# Transfer_Register.net
KiCad netlist of a schematic drawn in EAGLE
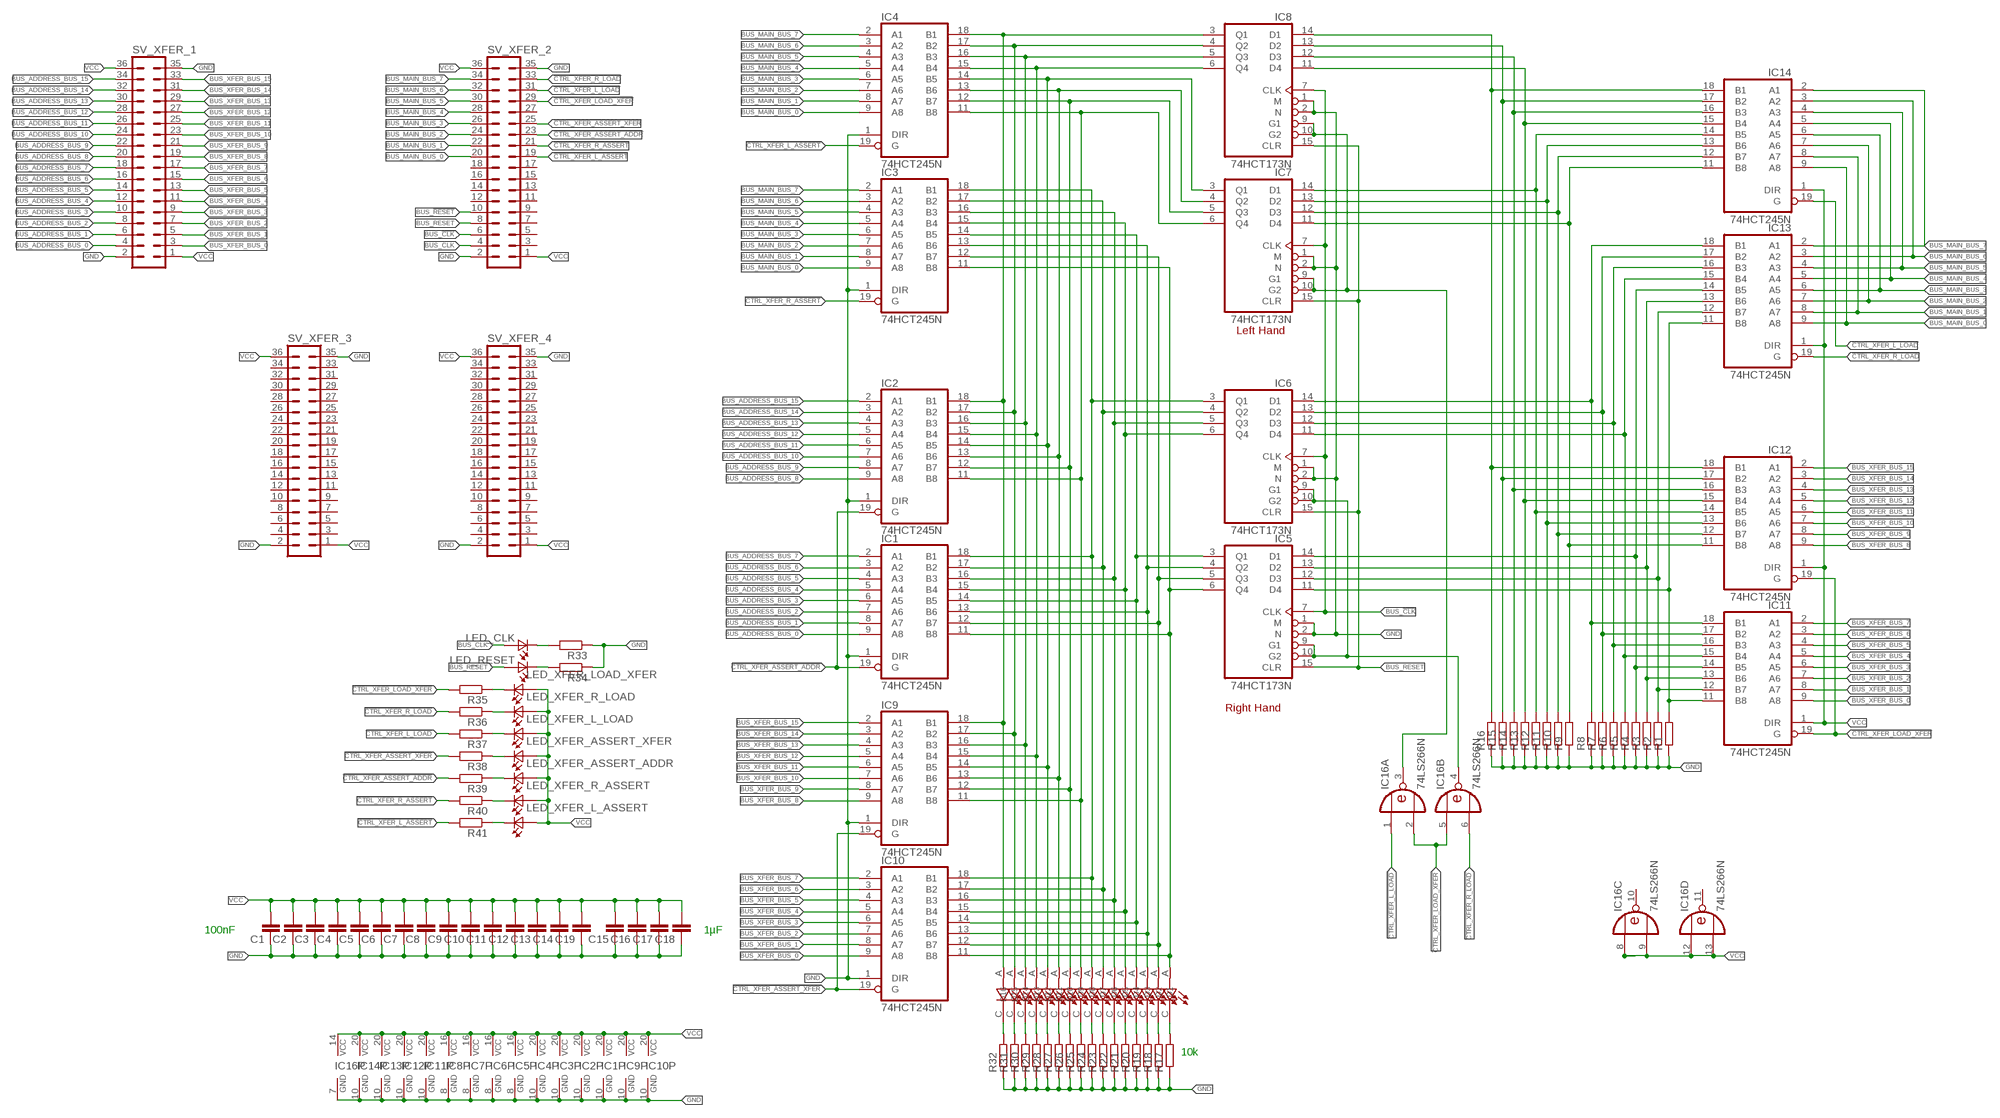
[diagram p0: schematic, sheet 1]

(export (version "E")
  (design (tool "Eeschema 10.0.6"))
  (components
    (comp (ref "C1")
      (value "C-EUC0805")
      (footprint "eagle-import:C0805")
      (libsource (lib "eagle-import") (part "C-EUC0805"))
    )
    (comp (ref "C2")
      (value "C-EUC0805")
      (footprint "eagle-import:C0805")
      (libsource (lib "eagle-import") (part "C-EUC0805"))
    )
    (comp (ref "C3")
      (value "C-EUC0805")
      (footprint "eagle-import:C0805")
      (libsource (lib "eagle-import") (part "C-EUC0805"))
    )
    (comp (ref "C4")
      (value "C-EUC0805")
      (footprint "eagle-import:C0805")
      (libsource (lib "eagle-import") (part "C-EUC0805"))
    )
    (comp (ref "C5")
      (value "C-EUC0805")
      (footprint "eagle-import:C0805")
      (libsource (lib "eagle-import") (part "C-EUC0805"))
    )
    (comp (ref "C6")
      (value "C-EUC0805")
      (footprint "eagle-import:C0805")
      (libsource (lib "eagle-import") (part "C-EUC0805"))
    )
    (comp (ref "C7")
      (value "C-EUC0805")
      (footprint "eagle-import:C0805")
      (libsource (lib "eagle-import") (part "C-EUC0805"))
    )
    (comp (ref "C8")
      (value "C-EUC0805")
      (footprint "eagle-import:C0805")
      (libsource (lib "eagle-import") (part "C-EUC0805"))
    )
    (comp (ref "C9")
      (value "C-EUC0805")
      (footprint "eagle-import:C0805")
      (libsource (lib "eagle-import") (part "C-EUC0805"))
    )
    (comp (ref "C10")
      (value "C-EUC0805")
      (footprint "eagle-import:C0805")
      (libsource (lib "eagle-import") (part "C-EUC0805"))
    )
    (comp (ref "C11")
      (value "C-EUC0805")
      (footprint "eagle-import:C0805")
      (libsource (lib "eagle-import") (part "C-EUC0805"))
    )
    (comp (ref "C12")
      (value "C-EUC0805")
      (footprint "eagle-import:C0805")
      (libsource (lib "eagle-import") (part "C-EUC0805"))
    )
    (comp (ref "C13")
      (value "C-EUC0805")
      (footprint "eagle-import:C0805")
      (libsource (lib "eagle-import") (part "C-EUC0805"))
    )
    (comp (ref "C14")
      (value "C-EUC0805")
      (footprint "eagle-import:C0805")
      (libsource (lib "eagle-import") (part "C-EUC0805"))
    )
    (comp (ref "C15")
      (value "C-EUC0805")
      (footprint "eagle-import:C0805")
      (libsource (lib "eagle-import") (part "C-EUC0805"))
    )
    (comp (ref "C16")
      (value "C-EUC0805")
      (footprint "eagle-import:C0805")
      (libsource (lib "eagle-import") (part "C-EUC0805"))
    )
    (comp (ref "C17")
      (value "C-EUC0805")
      (footprint "eagle-import:C0805")
      (libsource (lib "eagle-import") (part "C-EUC0805"))
    )
    (comp (ref "C18")
      (value "C-EUC0805")
      (footprint "eagle-import:C0805")
      (libsource (lib "eagle-import") (part "C-EUC0805"))
    )
    (comp (ref "C19")
      (value "C-EUC0805")
      (footprint "eagle-import:C0805")
      (libsource (lib "eagle-import") (part "C-EUC0805"))
    )
    (comp (ref "D1")
      (value "LTST-C193KRKT-5A")
      (footprint "eagle-import:LEDC1608X45N")
      (fields (field (name "MANUFACTURER") "Lite-On"))
      (libsource (lib "eagle-import") (part "LTST-C193KRKT-5A"))
    )
    (comp (ref "D2")
      (value "LTST-C193KRKT-5A")
      (footprint "eagle-import:LEDC1608X45N")
      (fields (field (name "MANUFACTURER") "Lite-On"))
      (libsource (lib "eagle-import") (part "LTST-C193KRKT-5A"))
    )
    (comp (ref "D3")
      (value "LTST-C193KRKT-5A")
      (footprint "eagle-import:LEDC1608X45N")
      (fields (field (name "MANUFACTURER") "Lite-On"))
      (libsource (lib "eagle-import") (part "LTST-C193KRKT-5A"))
    )
    (comp (ref "D4")
      (value "LTST-C193KRKT-5A")
      (footprint "eagle-import:LEDC1608X45N")
      (fields (field (name "MANUFACTURER") "Lite-On"))
      (libsource (lib "eagle-import") (part "LTST-C193KRKT-5A"))
    )
    (comp (ref "D5")
      (value "LTST-C193KRKT-5A")
      (footprint "eagle-import:LEDC1608X45N")
      (fields (field (name "MANUFACTURER") "Lite-On"))
      (libsource (lib "eagle-import") (part "LTST-C193KRKT-5A"))
    )
    (comp (ref "D6")
      (value "LTST-C193KRKT-5A")
      (footprint "eagle-import:LEDC1608X45N")
      (fields (field (name "MANUFACTURER") "Lite-On"))
      (libsource (lib "eagle-import") (part "LTST-C193KRKT-5A"))
    )
    (comp (ref "D7")
      (value "LTST-C193KRKT-5A")
      (footprint "eagle-import:LEDC1608X45N")
      (fields (field (name "MANUFACTURER") "Lite-On"))
      (libsource (lib "eagle-import") (part "LTST-C193KRKT-5A"))
    )
    (comp (ref "D8")
      (value "LTST-C193KRKT-5A")
      (footprint "eagle-import:LEDC1608X45N")
      (fields (field (name "MANUFACTURER") "Lite-On"))
      (libsource (lib "eagle-import") (part "LTST-C193KRKT-5A"))
    )
    (comp (ref "D9")
      (value "LTST-C193KRKT-5A")
      (footprint "eagle-import:LEDC1608X45N")
      (fields (field (name "MANUFACTURER") "Lite-On"))
      (libsource (lib "eagle-import") (part "LTST-C193KRKT-5A"))
    )
    (comp (ref "D10")
      (value "LTST-C193KRKT-5A")
      (footprint "eagle-import:LEDC1608X45N")
      (fields (field (name "MANUFACTURER") "Lite-On"))
      (libsource (lib "eagle-import") (part "LTST-C193KRKT-5A"))
    )
    (comp (ref "D11")
      (value "LTST-C193KRKT-5A")
      (footprint "eagle-import:LEDC1608X45N")
      (fields (field (name "MANUFACTURER") "Lite-On"))
      (libsource (lib "eagle-import") (part "LTST-C193KRKT-5A"))
    )
    (comp (ref "D12")
      (value "LTST-C193KRKT-5A")
      (footprint "eagle-import:LEDC1608X45N")
      (fields (field (name "MANUFACTURER") "Lite-On"))
      (libsource (lib "eagle-import") (part "LTST-C193KRKT-5A"))
    )
    (comp (ref "D13")
      (value "LTST-C193KRKT-5A")
      (footprint "eagle-import:LEDC1608X45N")
      (fields (field (name "MANUFACTURER") "Lite-On"))
      (libsource (lib "eagle-import") (part "LTST-C193KRKT-5A"))
    )
    (comp (ref "D14")
      (value "LTST-C193KRKT-5A")
      (footprint "eagle-import:LEDC1608X45N")
      (fields (field (name "MANUFACTURER") "Lite-On"))
      (libsource (lib "eagle-import") (part "LTST-C193KRKT-5A"))
    )
    (comp (ref "D15")
      (value "LTST-C193KRKT-5A")
      (footprint "eagle-import:LEDC1608X45N")
      (fields (field (name "MANUFACTURER") "Lite-On"))
      (libsource (lib "eagle-import") (part "LTST-C193KRKT-5A"))
    )
    (comp (ref "D16")
      (value "LTST-C193KRKT-5A")
      (footprint "eagle-import:LEDC1608X45N")
      (fields (field (name "MANUFACTURER") "Lite-On"))
      (libsource (lib "eagle-import") (part "LTST-C193KRKT-5A"))
    )
    (comp (ref "IC1")
      (value "74HCT245N")
      (footprint "eagle-import:DIL20")
      (libsource (lib "eagle-import") (part "74245NHCT"))
    )
    (comp (ref "IC2")
      (value "74HCT245N")
      (footprint "eagle-import:DIL20")
      (libsource (lib "eagle-import") (part "74245NHCT"))
    )
    (comp (ref "IC3")
      (value "74HCT245N")
      (footprint "eagle-import:DIL20")
      (libsource (lib "eagle-import") (part "74245NHCT"))
    )
    (comp (ref "IC4")
      (value "74HCT245N")
      (footprint "eagle-import:DIL20")
      (libsource (lib "eagle-import") (part "74245NHCT"))
    )
    (comp (ref "IC5")
      (value "74HCT173N")
      (footprint "eagle-import:DIL16")
      (libsource (lib "eagle-import") (part "74173NHCT"))
    )
    (comp (ref "IC6")
      (value "74HCT173N")
      (footprint "eagle-import:DIL16")
      (libsource (lib "eagle-import") (part "74173NHCT"))
    )
    (comp (ref "IC7")
      (value "74HCT173N")
      (footprint "eagle-import:DIL16")
      (libsource (lib "eagle-import") (part "74173NHCT"))
    )
    (comp (ref "IC8")
      (value "74HCT173N")
      (footprint "eagle-import:DIL16")
      (libsource (lib "eagle-import") (part "74173NHCT"))
    )
    (comp (ref "IC9")
      (value "74HCT245N")
      (footprint "eagle-import:DIL20")
      (libsource (lib "eagle-import") (part "74245NHCT"))
    )
    (comp (ref "IC10")
      (value "74HCT245N")
      (footprint "eagle-import:DIL20")
      (libsource (lib "eagle-import") (part "74245NHCT"))
    )
    (comp (ref "IC11")
      (value "74HCT245N")
      (footprint "eagle-import:DIL20")
      (libsource (lib "eagle-import") (part "74245NHCT"))
    )
    (comp (ref "IC12")
      (value "74HCT245N")
      (footprint "eagle-import:DIL20")
      (libsource (lib "eagle-import") (part "74245NHCT"))
    )
    (comp (ref "IC13")
      (value "74HCT245N")
      (footprint "eagle-import:DIL20")
      (libsource (lib "eagle-import") (part "74245NHCT"))
    )
    (comp (ref "IC14")
      (value "74HCT245N")
      (footprint "eagle-import:DIL20")
      (libsource (lib "eagle-import") (part "74245NHCT"))
    )
    (comp (ref "IC16")
      (value "74LS266N")
      (footprint "eagle-import:DIL14")
      (libsource (lib "eagle-import") (part "74266NLS"))
    )
    (comp (ref "LED_CLK")
      (value "LTST-C193TBKT-5A")
      (footprint "eagle-import:0603")
      (libsource (lib "eagle-import") (part "LTST-C193TBKT-5A"))
    )
    (comp (ref "LED_RESET")
      (value "LTST-C193TBKT-5A")
      (footprint "eagle-import:0603")
      (libsource (lib "eagle-import") (part "LTST-C193TBKT-5A"))
    )
    (comp (ref "LED_XFER_ASSERT_ADDR")
      (value "LTST-C193TBKT-5A")
      (footprint "eagle-import:0603")
      (libsource (lib "eagle-import") (part "LTST-C193TBKT-5A"))
    )
    (comp (ref "LED_XFER_ASSERT_XFER")
      (value "LTST-C193TBKT-5A")
      (footprint "eagle-import:0603")
      (libsource (lib "eagle-import") (part "LTST-C193TBKT-5A"))
    )
    (comp (ref "LED_XFER_LOAD_XFER")
      (value "LTST-C193TBKT-5A")
      (footprint "eagle-import:0603")
      (libsource (lib "eagle-import") (part "LTST-C193TBKT-5A"))
    )
    (comp (ref "LED_XFER_L_ASSERT")
      (value "LTST-C193TBKT-5A")
      (footprint "eagle-import:0603")
      (libsource (lib "eagle-import") (part "LTST-C193TBKT-5A"))
    )
    (comp (ref "LED_XFER_L_LOAD")
      (value "LTST-C193TBKT-5A")
      (footprint "eagle-import:0603")
      (libsource (lib "eagle-import") (part "LTST-C193TBKT-5A"))
    )
    (comp (ref "LED_XFER_R_ASSERT")
      (value "LTST-C193TBKT-5A")
      (footprint "eagle-import:0603")
      (libsource (lib "eagle-import") (part "LTST-C193TBKT-5A"))
    )
    (comp (ref "LED_XFER_R_LOAD")
      (value "LTST-C193TBKT-5A")
      (footprint "eagle-import:0603")
      (libsource (lib "eagle-import") (part "LTST-C193TBKT-5A"))
    )
    (comp (ref "R1")
      (value "R-EU_R0805")
      (footprint "eagle-import:R0805")
      (libsource (lib "eagle-import") (part "R-EU_R0805"))
    )
    (comp (ref "R2")
      (value "R-EU_R0805")
      (footprint "eagle-import:R0805")
      (libsource (lib "eagle-import") (part "R-EU_R0805"))
    )
    (comp (ref "R3")
      (value "R-EU_R0805")
      (footprint "eagle-import:R0805")
      (libsource (lib "eagle-import") (part "R-EU_R0805"))
    )
    (comp (ref "R4")
      (value "R-EU_R0805")
      (footprint "eagle-import:R0805")
      (libsource (lib "eagle-import") (part "R-EU_R0805"))
    )
    (comp (ref "R5")
      (value "R-EU_R0805")
      (footprint "eagle-import:R0805")
      (libsource (lib "eagle-import") (part "R-EU_R0805"))
    )
    (comp (ref "R6")
      (value "R-EU_R0805")
      (footprint "eagle-import:R0805")
      (libsource (lib "eagle-import") (part "R-EU_R0805"))
    )
    (comp (ref "R7")
      (value "R-EU_R0805")
      (footprint "eagle-import:R0805")
      (libsource (lib "eagle-import") (part "R-EU_R0805"))
    )
    (comp (ref "R8")
      (value "R-EU_R0805")
      (footprint "eagle-import:R0805")
      (libsource (lib "eagle-import") (part "R-EU_R0805"))
    )
    (comp (ref "R9")
      (value "R-EU_R0805")
      (footprint "eagle-import:R0805")
      (libsource (lib "eagle-import") (part "R-EU_R0805"))
    )
    (comp (ref "R10")
      (value "R-EU_R0805")
      (footprint "eagle-import:R0805")
      (libsource (lib "eagle-import") (part "R-EU_R0805"))
    )
    (comp (ref "R11")
      (value "R-EU_R0805")
      (footprint "eagle-import:R0805")
      (libsource (lib "eagle-import") (part "R-EU_R0805"))
    )
    (comp (ref "R12")
      (value "R-EU_R0805")
      (footprint "eagle-import:R0805")
      (libsource (lib "eagle-import") (part "R-EU_R0805"))
    )
    (comp (ref "R13")
      (value "R-EU_R0805")
      (footprint "eagle-import:R0805")
      (libsource (lib "eagle-import") (part "R-EU_R0805"))
    )
    (comp (ref "R14")
      (value "R-EU_R0805")
      (footprint "eagle-import:R0805")
      (libsource (lib "eagle-import") (part "R-EU_R0805"))
    )
    (comp (ref "R15")
      (value "R-EU_R0805")
      (footprint "eagle-import:R0805")
      (libsource (lib "eagle-import") (part "R-EU_R0805"))
    )
    (comp (ref "R16")
      (value "R-EU_R0805")
      (footprint "eagle-import:R0805")
      (libsource (lib "eagle-import") (part "R-EU_R0805"))
    )
    (comp (ref "R17")
      (value "R-EU_R0805")
      (footprint "eagle-import:R0805")
      (libsource (lib "eagle-import") (part "R-EU_R0805"))
    )
    (comp (ref "R18")
      (value "R-EU_R0805")
      (footprint "eagle-import:R0805")
      (libsource (lib "eagle-import") (part "R-EU_R0805"))
    )
    (comp (ref "R19")
      (value "R-EU_R0805")
      (footprint "eagle-import:R0805")
      (libsource (lib "eagle-import") (part "R-EU_R0805"))
    )
    (comp (ref "R20")
      (value "R-EU_R0805")
      (footprint "eagle-import:R0805")
      (libsource (lib "eagle-import") (part "R-EU_R0805"))
    )
    (comp (ref "R21")
      (value "R-EU_R0805")
      (footprint "eagle-import:R0805")
      (libsource (lib "eagle-import") (part "R-EU_R0805"))
    )
    (comp (ref "R22")
      (value "R-EU_R0805")
      (footprint "eagle-import:R0805")
      (libsource (lib "eagle-import") (part "R-EU_R0805"))
    )
    (comp (ref "R23")
      (value "R-EU_R0805")
      (footprint "eagle-import:R0805")
      (libsource (lib "eagle-import") (part "R-EU_R0805"))
    )
    (comp (ref "R24")
      (value "R-EU_R0805")
      (footprint "eagle-import:R0805")
      (libsource (lib "eagle-import") (part "R-EU_R0805"))
    )
    (comp (ref "R25")
      (value "R-EU_R0805")
      (footprint "eagle-import:R0805")
      (libsource (lib "eagle-import") (part "R-EU_R0805"))
    )
    (comp (ref "R26")
      (value "R-EU_R0805")
      (footprint "eagle-import:R0805")
      (libsource (lib "eagle-import") (part "R-EU_R0805"))
    )
    (comp (ref "R27")
      (value "R-EU_R0805")
      (footprint "eagle-import:R0805")
      (libsource (lib "eagle-import") (part "R-EU_R0805"))
    )
    (comp (ref "R28")
      (value "R-EU_R0805")
      (footprint "eagle-import:R0805")
      (libsource (lib "eagle-import") (part "R-EU_R0805"))
    )
    (comp (ref "R29")
      (value "R-EU_R0805")
      (footprint "eagle-import:R0805")
      (libsource (lib "eagle-import") (part "R-EU_R0805"))
    )
    (comp (ref "R30")
      (value "R-EU_R0805")
      (footprint "eagle-import:R0805")
      (libsource (lib "eagle-import") (part "R-EU_R0805"))
    )
    (comp (ref "R31")
      (value "R-EU_R0805")
      (footprint "eagle-import:R0805")
      (libsource (lib "eagle-import") (part "R-EU_R0805"))
    )
    (comp (ref "R32")
      (value "R-EU_R0805")
      (footprint "eagle-import:R0805")
      (libsource (lib "eagle-import") (part "R-EU_R0805"))
    )
    (comp (ref "R33")
      (value "R-EU_R0805")
      (footprint "eagle-import:R0805")
      (libsource (lib "eagle-import") (part "R-EU_R0805"))
    )
    (comp (ref "R34")
      (value "R-EU_R0805")
      (footprint "eagle-import:R0805")
      (libsource (lib "eagle-import") (part "R-EU_R0805"))
    )
    (comp (ref "R35")
      (value "R-EU_R0805")
      (footprint "eagle-import:R0805")
      (libsource (lib "eagle-import") (part "R-EU_R0805"))
    )
    (comp (ref "R36")
      (value "R-EU_R0805")
      (footprint "eagle-import:R0805")
      (libsource (lib "eagle-import") (part "R-EU_R0805"))
    )
    (comp (ref "R37")
      (value "R-EU_R0805")
      (footprint "eagle-import:R0805")
      (libsource (lib "eagle-import") (part "R-EU_R0805"))
    )
    (comp (ref "R38")
      (value "R-EU_R0805")
      (footprint "eagle-import:R0805")
      (libsource (lib "eagle-import") (part "R-EU_R0805"))
    )
    (comp (ref "R39")
      (value "R-EU_R0805")
      (footprint "eagle-import:R0805")
      (libsource (lib "eagle-import") (part "R-EU_R0805"))
    )
    (comp (ref "R40")
      (value "R-EU_R0805")
      (footprint "eagle-import:R0805")
      (libsource (lib "eagle-import") (part "R-EU_R0805"))
    )
    (comp (ref "R41")
      (value "R-EU_R0805")
      (footprint "eagle-import:R0805")
      (libsource (lib "eagle-import") (part "R-EU_R0805"))
    )
    (comp (ref "SV_XFER_1")
      (value "MA18-2")
      (footprint "eagle-import:MA18-2")
      (libsource (lib "eagle-import") (part "MA18-2"))
    )
    (comp (ref "SV_XFER_2")
      (value "MA18-2")
      (footprint "eagle-import:MA18-2")
      (libsource (lib "eagle-import") (part "MA18-2"))
    )
    (comp (ref "SV_XFER_3")
      (value "MA18-2")
      (footprint "eagle-import:MA18-2")
      (libsource (lib "eagle-import") (part "MA18-2"))
    )
    (comp (ref "SV_XFER_4")
      (value "MA18-2")
      (footprint "eagle-import:MA18-2")
      (libsource (lib "eagle-import") (part "MA18-2"))
    )
  )
  (nets
    (net (code "1") (name "/BUS_~{CLK}") (class "Default")
      (node (ref "IC5") (pin "7") (pinfunction "CLK_7") (pintype "input"))
      (node (ref "IC6") (pin "7") (pinfunction "CLK_7") (pintype "input"))
      (node (ref "IC7") (pin "7") (pinfunction "CLK_7") (pintype "input"))
      (node (ref "IC8") (pin "7") (pinfunction "CLK_7") (pintype "input"))
      (node (ref "SV_XFER_2") (pin "6") (pinfunction "6_6") (pintype "passive"))
    )
    (net (code "2") (name "/BUS_~{RESET}") (class "Default")
      (node (ref "SV_XFER_2") (pin "10") (pinfunction "10_10") (pintype "passive"))
    )
    (net (code "3") (name "/~{CTRL_XFER_ASSERT_ADDR}") (class "Default")
      (node (ref "IC1") (pin "19") (pinfunction "G_19") (pintype "input"))
      (node (ref "IC2") (pin "19") (pinfunction "G_19") (pintype "input"))
      (node (ref "R39") (pin "2") (pinfunction "2_2") (pintype "passive"))
      (node (ref "SV_XFER_2") (pin "23") (pinfunction "23_23") (pintype "passive"))
    )
    (net (code "4") (name "/~{CTRL_XFER_ASSERT_XFER}") (class "Default")
      (node (ref "IC10") (pin "19") (pinfunction "G_19") (pintype "input"))
      (node (ref "IC9") (pin "19") (pinfunction "G_19") (pintype "input"))
      (node (ref "R38") (pin "2") (pinfunction "2_2") (pintype "passive"))
      (node (ref "SV_XFER_2") (pin "25") (pinfunction "25_25") (pintype "passive"))
    )
    (net (code "5") (name "/~{CTRL_XFER_LOAD_XFER}") (class "Default")
      (node (ref "IC11") (pin "19") (pinfunction "G_19") (pintype "input"))
      (node (ref "IC12") (pin "19") (pinfunction "G_19") (pintype "input"))
      (node (ref "IC16") (pin "2") (pinfunction "I1_2") (pintype "input"))
      (node (ref "IC16") (pin "5") (pinfunction "I0_5") (pintype "input"))
      (node (ref "R35") (pin "2") (pinfunction "2_2") (pintype "passive"))
      (node (ref "SV_XFER_2") (pin "29") (pinfunction "29_29") (pintype "passive"))
    )
    (net (code "6") (name "/~{CTRL_XFER_L_ASSERT}") (class "Default")
      (node (ref "IC4") (pin "19") (pinfunction "G_19") (pintype "input"))
      (node (ref "R41") (pin "2") (pinfunction "2_2") (pintype "passive"))
      (node (ref "SV_XFER_2") (pin "19") (pinfunction "19_19") (pintype "passive"))
    )
    (net (code "7") (name "/~{CTRL_XFER_L_LOAD}") (class "Default")
      (node (ref "IC14") (pin "19") (pinfunction "G_19") (pintype "input"))
      (node (ref "IC16") (pin "1") (pinfunction "I0_1") (pintype "input"))
      (node (ref "R37") (pin "2") (pinfunction "2_2") (pintype "passive"))
      (node (ref "SV_XFER_2") (pin "31") (pinfunction "31_31") (pintype "passive"))
    )
    (net (code "8") (name "/~{CTRL_XFER_R_ASSERT}") (class "Default")
      (node (ref "IC3") (pin "19") (pinfunction "G_19") (pintype "input"))
      (node (ref "R40") (pin "2") (pinfunction "2_2") (pintype "passive"))
      (node (ref "SV_XFER_2") (pin "21") (pinfunction "21_21") (pintype "passive"))
    )
    (net (code "9") (name "/~{CTRL_XFER_R_LOAD}") (class "Default")
      (node (ref "IC13") (pin "19") (pinfunction "G_19") (pintype "input"))
      (node (ref "IC16") (pin "6") (pinfunction "I1_6") (pintype "input"))
      (node (ref "R36") (pin "2") (pinfunction "2_2") (pintype "passive"))
      (node (ref "SV_XFER_2") (pin "33") (pinfunction "33_33") (pintype "passive"))
    )
    (net (code "10") (name "BUS_ADDRESS_BUS_0") (class "Default")
      (node (ref "IC1") (pin "9") (pinfunction "A8_9") (pintype "bidirectional"))
      (node (ref "SV_XFER_1") (pin "4") (pinfunction "4_4") (pintype "passive"))
    )
    (net (code "11") (name "BUS_ADDRESS_BUS_1") (class "Default")
      (node (ref "IC1") (pin "8") (pinfunction "A7_8") (pintype "bidirectional"))
      (node (ref "SV_XFER_1") (pin "6") (pinfunction "6_6") (pintype "passive"))
    )
    (net (code "12") (name "BUS_ADDRESS_BUS_2") (class "Default")
      (node (ref "IC1") (pin "7") (pinfunction "A6_7") (pintype "bidirectional"))
      (node (ref "SV_XFER_1") (pin "8") (pinfunction "8_8") (pintype "passive"))
    )
    (net (code "13") (name "BUS_ADDRESS_BUS_3") (class "Default")
      (node (ref "IC1") (pin "6") (pinfunction "A5_6") (pintype "bidirectional"))
      (node (ref "SV_XFER_1") (pin "10") (pinfunction "10_10") (pintype "passive"))
    )
    (net (code "14") (name "BUS_ADDRESS_BUS_4") (class "Default")
      (node (ref "IC1") (pin "5") (pinfunction "A4_5") (pintype "bidirectional"))
      (node (ref "SV_XFER_1") (pin "12") (pinfunction "12_12") (pintype "passive"))
    )
    (net (code "15") (name "BUS_ADDRESS_BUS_5") (class "Default")
      (node (ref "IC1") (pin "4") (pinfunction "A3_4") (pintype "bidirectional"))
      (node (ref "SV_XFER_1") (pin "14") (pinfunction "14_14") (pintype "passive"))
    )
    (net (code "16") (name "BUS_ADDRESS_BUS_6") (class "Default")
      (node (ref "IC1") (pin "3") (pinfunction "A2_3") (pintype "bidirectional"))
      (node (ref "SV_XFER_1") (pin "16") (pinfunction "16_16") (pintype "passive"))
    )
    (net (code "17") (name "BUS_ADDRESS_BUS_7") (class "Default")
      (node (ref "IC1") (pin "2") (pinfunction "A1_2") (pintype "bidirectional"))
      (node (ref "SV_XFER_1") (pin "18") (pinfunction "18_18") (pintype "passive"))
    )
    (net (code "18") (name "BUS_ADDRESS_BUS_8") (class "Default")
      (node (ref "IC2") (pin "9") (pinfunction "A8_9") (pintype "bidirectional"))
      (node (ref "SV_XFER_1") (pin "20") (pinfunction "20_20") (pintype "passive"))
    )
    (net (code "19") (name "BUS_ADDRESS_BUS_9") (class "Default")
      (node (ref "IC2") (pin "8") (pinfunction "A7_8") (pintype "bidirectional"))
      (node (ref "SV_XFER_1") (pin "22") (pinfunction "22_22") (pintype "passive"))
    )
    (net (code "20") (name "BUS_ADDRESS_BUS_10") (class "Default")
      (node (ref "IC2") (pin "7") (pinfunction "A6_7") (pintype "bidirectional"))
      (node (ref "SV_XFER_1") (pin "24") (pinfunction "24_24") (pintype "passive"))
    )
    (net (code "21") (name "BUS_ADDRESS_BUS_11") (class "Default")
      (node (ref "IC2") (pin "6") (pinfunction "A5_6") (pintype "bidirectional"))
      (node (ref "SV_XFER_1") (pin "26") (pinfunction "26_26") (pintype "passive"))
    )
    (net (code "22") (name "BUS_ADDRESS_BUS_12") (class "Default")
      (node (ref "IC2") (pin "5") (pinfunction "A4_5") (pintype "bidirectional"))
      (node (ref "SV_XFER_1") (pin "28") (pinfunction "28_28") (pintype "passive"))
    )
    (net (code "23") (name "BUS_ADDRESS_BUS_13") (class "Default")
      (node (ref "IC2") (pin "4") (pinfunction "A3_4") (pintype "bidirectional"))
      (node (ref "SV_XFER_1") (pin "30") (pinfunction "30_30") (pintype "passive"))
    )
    (net (code "24") (name "BUS_ADDRESS_BUS_14") (class "Default")
      (node (ref "IC2") (pin "3") (pinfunction "A2_3") (pintype "bidirectional"))
      (node (ref "SV_XFER_1") (pin "32") (pinfunction "32_32") (pintype "passive"))
    )
    (net (code "25") (name "BUS_ADDRESS_BUS_15") (class "Default")
      (node (ref "IC2") (pin "2") (pinfunction "A1_2") (pintype "bidirectional"))
      (node (ref "SV_XFER_1") (pin "34") (pinfunction "34_34") (pintype "passive"))
    )
    (net (code "26") (name "BUS_CLK") (class "Default")
      (node (ref "LED_CLK") (pin "2") (pinfunction "A2_2") (pintype "passive"))
      (node (ref "SV_XFER_2") (pin "4") (pinfunction "4_4") (pintype "passive"))
    )
    (net (code "27") (name "BUS_MAIN_BUS_0") (class "Default")
      (node (ref "IC13") (pin "9") (pinfunction "A8_9") (pintype "bidirectional"))
      (node (ref "IC14") (pin "9") (pinfunction "A8_9") (pintype "bidirectional"))
      (node (ref "IC3") (pin "9") (pinfunction "A8_9") (pintype "bidirectional"))
      (node (ref "IC4") (pin "9") (pinfunction "A8_9") (pintype "bidirectional"))
      (node (ref "SV_XFER_2") (pin "20") (pinfunction "20_20") (pintype "passive"))
    )
    (net (code "28") (name "BUS_MAIN_BUS_1") (class "Default")
      (node (ref "IC13") (pin "8") (pinfunction "A7_8") (pintype "bidirectional"))
      (node (ref "IC14") (pin "8") (pinfunction "A7_8") (pintype "bidirectional"))
      (node (ref "IC3") (pin "8") (pinfunction "A7_8") (pintype "bidirectional"))
      (node (ref "IC4") (pin "8") (pinfunction "A7_8") (pintype "bidirectional"))
      (node (ref "SV_XFER_2") (pin "22") (pinfunction "22_22") (pintype "passive"))
    )
    (net (code "29") (name "BUS_MAIN_BUS_2") (class "Default")
      (node (ref "IC13") (pin "7") (pinfunction "A6_7") (pintype "bidirectional"))
      (node (ref "IC14") (pin "7") (pinfunction "A6_7") (pintype "bidirectional"))
      (node (ref "IC3") (pin "7") (pinfunction "A6_7") (pintype "bidirectional"))
      (node (ref "IC4") (pin "7") (pinfunction "A6_7") (pintype "bidirectional"))
      (node (ref "SV_XFER_2") (pin "24") (pinfunction "24_24") (pintype "passive"))
    )
    (net (code "30") (name "BUS_MAIN_BUS_3") (class "Default")
      (node (ref "IC13") (pin "6") (pinfunction "A5_6") (pintype "bidirectional"))
      (node (ref "IC14") (pin "6") (pinfunction "A5_6") (pintype "bidirectional"))
      (node (ref "IC3") (pin "6") (pinfunction "A5_6") (pintype "bidirectional"))
      (node (ref "IC4") (pin "6") (pinfunction "A5_6") (pintype "bidirectional"))
      (node (ref "SV_XFER_2") (pin "26") (pinfunction "26_26") (pintype "passive"))
    )
    (net (code "31") (name "BUS_MAIN_BUS_4") (class "Default")
      (node (ref "IC13") (pin "5") (pinfunction "A4_5") (pintype "bidirectional"))
      (node (ref "IC14") (pin "5") (pinfunction "A4_5") (pintype "bidirectional"))
      (node (ref "IC3") (pin "5") (pinfunction "A4_5") (pintype "bidirectional"))
      (node (ref "IC4") (pin "5") (pinfunction "A4_5") (pintype "bidirectional"))
      (node (ref "SV_XFER_2") (pin "28") (pinfunction "28_28") (pintype "passive"))
    )
    (net (code "32") (name "BUS_MAIN_BUS_5") (class "Default")
      (node (ref "IC13") (pin "4") (pinfunction "A3_4") (pintype "bidirectional"))
      (node (ref "IC14") (pin "4") (pinfunction "A3_4") (pintype "bidirectional"))
      (node (ref "IC3") (pin "4") (pinfunction "A3_4") (pintype "bidirectional"))
      (node (ref "IC4") (pin "4") (pinfunction "A3_4") (pintype "bidirectional"))
      (node (ref "SV_XFER_2") (pin "30") (pinfunction "30_30") (pintype "passive"))
    )
    (net (code "33") (name "BUS_MAIN_BUS_6") (class "Default")
      (node (ref "IC13") (pin "3") (pinfunction "A2_3") (pintype "bidirectional"))
      (node (ref "IC14") (pin "3") (pinfunction "A2_3") (pintype "bidirectional"))
      (node (ref "IC3") (pin "3") (pinfunction "A2_3") (pintype "bidirectional"))
      (node (ref "IC4") (pin "3") (pinfunction "A2_3") (pintype "bidirectional"))
      (node (ref "SV_XFER_2") (pin "32") (pinfunction "32_32") (pintype "passive"))
    )
    (net (code "34") (name "BUS_MAIN_BUS_7") (class "Default")
      (node (ref "IC13") (pin "2") (pinfunction "A1_2") (pintype "bidirectional"))
      (node (ref "IC14") (pin "2") (pinfunction "A1_2") (pintype "bidirectional"))
      (node (ref "IC3") (pin "2") (pinfunction "A1_2") (pintype "bidirectional"))
      (node (ref "IC4") (pin "2") (pinfunction "A1_2") (pintype "bidirectional"))
      (node (ref "SV_XFER_2") (pin "34") (pinfunction "34_34") (pintype "passive"))
    )
    (net (code "35") (name "BUS_RESET") (class "Default")
      (node (ref "IC5") (pin "15") (pinfunction "CLR_15") (pintype "input"))
      (node (ref "IC6") (pin "15") (pinfunction "CLR_15") (pintype "input"))
      (node (ref "IC7") (pin "15") (pinfunction "CLR_15") (pintype "input"))
      (node (ref "IC8") (pin "15") (pinfunction "CLR_15") (pintype "input"))
      (node (ref "LED_RESET") (pin "2") (pinfunction "A2_2") (pintype "passive"))
      (node (ref "SV_XFER_2") (pin "8") (pinfunction "8_8") (pintype "passive"))
    )
    (net (code "36") (name "BUS_XFER_BUS_0") (class "Default")
      (node (ref "IC10") (pin "9") (pinfunction "A8_9") (pintype "bidirectional"))
      (node (ref "IC11") (pin "9") (pinfunction "A8_9") (pintype "bidirectional"))
      (node (ref "SV_XFER_1") (pin "3") (pinfunction "3_3") (pintype "passive"))
    )
    (net (code "37") (name "BUS_XFER_BUS_1") (class "Default")
      (node (ref "IC10") (pin "8") (pinfunction "A7_8") (pintype "bidirectional"))
      (node (ref "IC11") (pin "8") (pinfunction "A7_8") (pintype "bidirectional"))
      (node (ref "SV_XFER_1") (pin "5") (pinfunction "5_5") (pintype "passive"))
    )
    (net (code "38") (name "BUS_XFER_BUS_2") (class "Default")
      (node (ref "IC10") (pin "7") (pinfunction "A6_7") (pintype "bidirectional"))
      (node (ref "IC11") (pin "7") (pinfunction "A6_7") (pintype "bidirectional"))
      (node (ref "SV_XFER_1") (pin "7") (pinfunction "7_7") (pintype "passive"))
    )
    (net (code "39") (name "BUS_XFER_BUS_3") (class "Default")
      (node (ref "IC10") (pin "6") (pinfunction "A5_6") (pintype "bidirectional"))
      (node (ref "IC11") (pin "6") (pinfunction "A5_6") (pintype "bidirectional"))
      (node (ref "SV_XFER_1") (pin "9") (pinfunction "9_9") (pintype "passive"))
    )
    (net (code "40") (name "BUS_XFER_BUS_4") (class "Default")
      (node (ref "IC10") (pin "5") (pinfunction "A4_5") (pintype "bidirectional"))
      (node (ref "IC11") (pin "5") (pinfunction "A4_5") (pintype "bidirectional"))
      (node (ref "SV_XFER_1") (pin "11") (pinfunction "11_11") (pintype "passive"))
    )
    (net (code "41") (name "BUS_XFER_BUS_5") (class "Default")
      (node (ref "IC10") (pin "4") (pinfunction "A3_4") (pintype "bidirectional"))
      (node (ref "IC11") (pin "4") (pinfunction "A3_4") (pintype "bidirectional"))
      (node (ref "SV_XFER_1") (pin "13") (pinfunction "13_13") (pintype "passive"))
    )
    (net (code "42") (name "BUS_XFER_BUS_6") (class "Default")
      (node (ref "IC10") (pin "3") (pinfunction "A2_3") (pintype "bidirectional"))
      (node (ref "IC11") (pin "3") (pinfunction "A2_3") (pintype "bidirectional"))
      (node (ref "SV_XFER_1") (pin "15") (pinfunction "15_15") (pintype "passive"))
    )
    (net (code "43") (name "BUS_XFER_BUS_7") (class "Default")
      (node (ref "IC10") (pin "2") (pinfunction "A1_2") (pintype "bidirectional"))
      (node (ref "IC11") (pin "2") (pinfunction "A1_2") (pintype "bidirectional"))
      (node (ref "SV_XFER_1") (pin "17") (pinfunction "17_17") (pintype "passive"))
    )
    (net (code "44") (name "BUS_XFER_BUS_8") (class "Default")
      (node (ref "IC12") (pin "9") (pinfunction "A8_9") (pintype "bidirectional"))
      (node (ref "IC9") (pin "9") (pinfunction "A8_9") (pintype "bidirectional"))
      (node (ref "SV_XFER_1") (pin "19") (pinfunction "19_19") (pintype "passive"))
    )
    (net (code "45") (name "BUS_XFER_BUS_9") (class "Default")
      (node (ref "IC12") (pin "8") (pinfunction "A7_8") (pintype "bidirectional"))
      (node (ref "IC9") (pin "8") (pinfunction "A7_8") (pintype "bidirectional"))
      (node (ref "SV_XFER_1") (pin "21") (pinfunction "21_21") (pintype "passive"))
    )
    (net (code "46") (name "BUS_XFER_BUS_10") (class "Default")
      (node (ref "IC12") (pin "7") (pinfunction "A6_7") (pintype "bidirectional"))
      (node (ref "IC9") (pin "7") (pinfunction "A6_7") (pintype "bidirectional"))
      (node (ref "SV_XFER_1") (pin "23") (pinfunction "23_23") (pintype "passive"))
    )
    (net (code "47") (name "BUS_XFER_BUS_11") (class "Default")
      (node (ref "IC12") (pin "6") (pinfunction "A5_6") (pintype "bidirectional"))
      (node (ref "IC9") (pin "6") (pinfunction "A5_6") (pintype "bidirectional"))
      (node (ref "SV_XFER_1") (pin "25") (pinfunction "25_25") (pintype "passive"))
    )
    (net (code "48") (name "BUS_XFER_BUS_12") (class "Default")
      (node (ref "IC12") (pin "5") (pinfunction "A4_5") (pintype "bidirectional"))
      (node (ref "IC9") (pin "5") (pinfunction "A4_5") (pintype "bidirectional"))
      (node (ref "SV_XFER_1") (pin "27") (pinfunction "27_27") (pintype "passive"))
    )
    (net (code "49") (name "BUS_XFER_BUS_13") (class "Default")
      (node (ref "IC12") (pin "4") (pinfunction "A3_4") (pintype "bidirectional"))
      (node (ref "IC9") (pin "4") (pinfunction "A3_4") (pintype "bidirectional"))
      (node (ref "SV_XFER_1") (pin "29") (pinfunction "29_29") (pintype "passive"))
    )
    (net (code "50") (name "BUS_XFER_BUS_14") (class "Default")
      (node (ref "IC12") (pin "3") (pinfunction "A2_3") (pintype "bidirectional"))
      (node (ref "IC9") (pin "3") (pinfunction "A2_3") (pintype "bidirectional"))
      (node (ref "SV_XFER_1") (pin "31") (pinfunction "31_31") (pintype "passive"))
    )
    (net (code "51") (name "BUS_XFER_BUS_15") (class "Default")
      (node (ref "IC12") (pin "2") (pinfunction "A1_2") (pintype "bidirectional"))
      (node (ref "IC9") (pin "2") (pinfunction "A1_2") (pintype "bidirectional"))
      (node (ref "SV_XFER_1") (pin "33") (pinfunction "33_33") (pintype "passive"))
    )
    (net (code "52") (name "GND") (class "Default")
      (node (ref "C1") (pin "1") (pinfunction "1_1") (pintype "passive"))
      (node (ref "C10") (pin "1") (pinfunction "1_1") (pintype "passive"))
      (node (ref "C11") (pin "1") (pinfunction "1_1") (pintype "passive"))
      (node (ref "C12") (pin "1") (pinfunction "1_1") (pintype "passive"))
      (node (ref "C13") (pin "1") (pinfunction "1_1") (pintype "passive"))
      (node (ref "C14") (pin "1") (pinfunction "1_1") (pintype "passive"))
      (node (ref "C15") (pin "1") (pinfunction "1_1") (pintype "passive"))
      (node (ref "C16") (pin "1") (pinfunction "1_1") (pintype "passive"))
      (node (ref "C17") (pin "1") (pinfunction "1_1") (pintype "passive"))
      (node (ref "C18") (pin "1") (pinfunction "1_1") (pintype "passive"))
      (node (ref "C19") (pin "1") (pinfunction "1_1") (pintype "passive"))
      (node (ref "C2") (pin "1") (pinfunction "1_1") (pintype "passive"))
      (node (ref "C3") (pin "1") (pinfunction "1_1") (pintype "passive"))
      (node (ref "C4") (pin "1") (pinfunction "1_1") (pintype "passive"))
      (node (ref "C5") (pin "1") (pinfunction "1_1") (pintype "passive"))
      (node (ref "C6") (pin "1") (pinfunction "1_1") (pintype "passive"))
      (node (ref "C7") (pin "1") (pinfunction "1_1") (pintype "passive"))
      (node (ref "C8") (pin "1") (pinfunction "1_1") (pintype "passive"))
      (node (ref "C9") (pin "1") (pinfunction "1_1") (pintype "passive"))
      (node (ref "IC1") (pin "1") (pinfunction "DIR_1") (pintype "input"))
      (node (ref "IC1") (pin "10") (pinfunction "GND_10") (pintype "power_in"))
      (node (ref "IC10") (pin "1") (pinfunction "DIR_1") (pintype "input"))
      (node (ref "IC10") (pin "10") (pinfunction "GND_10") (pintype "power_in"))
      (node (ref "IC11") (pin "10") (pinfunction "GND_10") (pintype "power_in"))
      (node (ref "IC12") (pin "10") (pinfunction "GND_10") (pintype "power_in"))
      (node (ref "IC13") (pin "10") (pinfunction "GND_10") (pintype "power_in"))
      (node (ref "IC14") (pin "10") (pinfunction "GND_10") (pintype "power_in"))
      (node (ref "IC16") (pin "7") (pinfunction "GND_7") (pintype "power_in"))
      (node (ref "IC2") (pin "1") (pinfunction "DIR_1") (pintype "input"))
      (node (ref "IC2") (pin "10") (pinfunction "GND_10") (pintype "power_in"))
      (node (ref "IC3") (pin "1") (pinfunction "DIR_1") (pintype "input"))
      (node (ref "IC3") (pin "10") (pinfunction "GND_10") (pintype "power_in"))
      (node (ref "IC4") (pin "1") (pinfunction "DIR_1") (pintype "input"))
      (node (ref "IC4") (pin "10") (pinfunction "GND_10") (pintype "power_in"))
      (node (ref "IC5") (pin "1") (pinfunction "M_1") (pintype "input"))
      (node (ref "IC5") (pin "2") (pinfunction "N_2") (pintype "input"))
      (node (ref "IC5") (pin "8") (pinfunction "GND_8") (pintype "power_in"))
      (node (ref "IC6") (pin "1") (pinfunction "M_1") (pintype "input"))
      (node (ref "IC6") (pin "2") (pinfunction "N_2") (pintype "input"))
      (node (ref "IC6") (pin "8") (pinfunction "GND_8") (pintype "power_in"))
      (node (ref "IC7") (pin "1") (pinfunction "M_1") (pintype "input"))
      (node (ref "IC7") (pin "2") (pinfunction "N_2") (pintype "input"))
      (node (ref "IC7") (pin "8") (pinfunction "GND_8") (pintype "power_in"))
      (node (ref "IC8") (pin "1") (pinfunction "M_1") (pintype "input"))
      (node (ref "IC8") (pin "2") (pinfunction "N_2") (pintype "input"))
      (node (ref "IC8") (pin "8") (pinfunction "GND_8") (pintype "power_in"))
      (node (ref "IC9") (pin "1") (pinfunction "DIR_1") (pintype "input"))
      (node (ref "IC9") (pin "10") (pinfunction "GND_10") (pintype "power_in"))
      (node (ref "R1") (pin "1") (pinfunction "1_1") (pintype "passive"))
      (node (ref "R10") (pin "1") (pinfunction "1_1") (pintype "passive"))
      (node (ref "R11") (pin "1") (pinfunction "1_1") (pintype "passive"))
      (node (ref "R12") (pin "1") (pinfunction "1_1") (pintype "passive"))
      (node (ref "R13") (pin "1") (pinfunction "1_1") (pintype "passive"))
      (node (ref "R14") (pin "1") (pinfunction "1_1") (pintype "passive"))
      (node (ref "R15") (pin "1") (pinfunction "1_1") (pintype "passive"))
      (node (ref "R16") (pin "1") (pinfunction "1_1") (pintype "passive"))
      (node (ref "R17") (pin "1") (pinfunction "1_1") (pintype "passive"))
      (node (ref "R18") (pin "1") (pinfunction "1_1") (pintype "passive"))
      (node (ref "R19") (pin "1") (pinfunction "1_1") (pintype "passive"))
      (node (ref "R2") (pin "1") (pinfunction "1_1") (pintype "passive"))
      (node (ref "R20") (pin "1") (pinfunction "1_1") (pintype "passive"))
      (node (ref "R21") (pin "1") (pinfunction "1_1") (pintype "passive"))
      (node (ref "R22") (pin "1") (pinfunction "1_1") (pintype "passive"))
      (node (ref "R23") (pin "1") (pinfunction "1_1") (pintype "passive"))
      (node (ref "R24") (pin "1") (pinfunction "1_1") (pintype "passive"))
      (node (ref "R25") (pin "1") (pinfunction "1_1") (pintype "passive"))
      (node (ref "R26") (pin "1") (pinfunction "1_1") (pintype "passive"))
      (node (ref "R27") (pin "1") (pinfunction "1_1") (pintype "passive"))
      (node (ref "R28") (pin "1") (pinfunction "1_1") (pintype "passive"))
      (node (ref "R29") (pin "1") (pinfunction "1_1") (pintype "passive"))
      (node (ref "R3") (pin "1") (pinfunction "1_1") (pintype "passive"))
      (node (ref "R30") (pin "1") (pinfunction "1_1") (pintype "passive"))
      (node (ref "R31") (pin "1") (pinfunction "1_1") (pintype "passive"))
      (node (ref "R32") (pin "1") (pinfunction "1_1") (pintype "passive"))
      (node (ref "R33") (pin "1") (pinfunction "1_1") (pintype "passive"))
      (node (ref "R34") (pin "1") (pinfunction "1_1") (pintype "passive"))
      (node (ref "R4") (pin "1") (pinfunction "1_1") (pintype "passive"))
      (node (ref "R5") (pin "1") (pinfunction "1_1") (pintype "passive"))
      (node (ref "R6") (pin "1") (pinfunction "1_1") (pintype "passive"))
      (node (ref "R7") (pin "1") (pinfunction "1_1") (pintype "passive"))
      (node (ref "R8") (pin "1") (pinfunction "1_1") (pintype "passive"))
      (node (ref "R9") (pin "1") (pinfunction "1_1") (pintype "passive"))
      (node (ref "SV_XFER_1") (pin "2") (pinfunction "2_2") (pintype "passive"))
      (node (ref "SV_XFER_1") (pin "35") (pinfunction "35_35") (pintype "passive"))
      (node (ref "SV_XFER_2") (pin "2") (pinfunction "2_2") (pintype "passive"))
      (node (ref "SV_XFER_2") (pin "35") (pinfunction "35_35") (pintype "passive"))
      (node (ref "SV_XFER_3") (pin "2") (pinfunction "2_2") (pintype "passive"))
      (node (ref "SV_XFER_3") (pin "35") (pinfunction "35_35") (pintype "passive"))
      (node (ref "SV_XFER_4") (pin "2") (pinfunction "2_2") (pintype "passive"))
      (node (ref "SV_XFER_4") (pin "35") (pinfunction "35_35") (pintype "passive"))
    )
    (net (code "53") (name "Net-(D1-PadC)") (class "Default")
      (node (ref "D1") (pin "C") (pinfunction "C_C") (pintype "passive"))
      (node (ref "R17") (pin "2") (pinfunction "2_2") (pintype "passive"))
    )
    (net (code "54") (name "Net-(D2-PadC)") (class "Default")
      (node (ref "D2") (pin "C") (pinfunction "C_C") (pintype "passive"))
      (node (ref "R18") (pin "2") (pinfunction "2_2") (pintype "passive"))
    )
    (net (code "55") (name "Net-(D3-PadC)") (class "Default")
      (node (ref "D3") (pin "C") (pinfunction "C_C") (pintype "passive"))
      (node (ref "R19") (pin "2") (pinfunction "2_2") (pintype "passive"))
    )
    (net (code "56") (name "Net-(D4-PadC)") (class "Default")
      (node (ref "D4") (pin "C") (pinfunction "C_C") (pintype "passive"))
      (node (ref "R20") (pin "2") (pinfunction "2_2") (pintype "passive"))
    )
    (net (code "57") (name "Net-(D5-PadC)") (class "Default")
      (node (ref "D5") (pin "C") (pinfunction "C_C") (pintype "passive"))
      (node (ref "R21") (pin "2") (pinfunction "2_2") (pintype "passive"))
    )
    (net (code "58") (name "Net-(D6-PadC)") (class "Default")
      (node (ref "D6") (pin "C") (pinfunction "C_C") (pintype "passive"))
      (node (ref "R22") (pin "2") (pinfunction "2_2") (pintype "passive"))
    )
    (net (code "59") (name "Net-(D7-PadC)") (class "Default")
      (node (ref "D7") (pin "C") (pinfunction "C_C") (pintype "passive"))
      (node (ref "R23") (pin "2") (pinfunction "2_2") (pintype "passive"))
    )
    (net (code "60") (name "Net-(D8-PadC)") (class "Default")
      (node (ref "D8") (pin "C") (pinfunction "C_C") (pintype "passive"))
      (node (ref "R24") (pin "2") (pinfunction "2_2") (pintype "passive"))
    )
    (net (code "61") (name "Net-(D9-PadC)") (class "Default")
      (node (ref "D9") (pin "C") (pinfunction "C_C") (pintype "passive"))
      (node (ref "R25") (pin "2") (pinfunction "2_2") (pintype "passive"))
    )
    (net (code "62") (name "Net-(D10-PadC)") (class "Default")
      (node (ref "D10") (pin "C") (pinfunction "C_C") (pintype "passive"))
      (node (ref "R26") (pin "2") (pinfunction "2_2") (pintype "passive"))
    )
    (net (code "63") (name "Net-(D11-PadC)") (class "Default")
      (node (ref "D11") (pin "C") (pinfunction "C_C") (pintype "passive"))
      (node (ref "R27") (pin "2") (pinfunction "2_2") (pintype "passive"))
    )
    (net (code "64") (name "Net-(D12-PadC)") (class "Default")
      (node (ref "D12") (pin "C") (pinfunction "C_C") (pintype "passive"))
      (node (ref "R28") (pin "2") (pinfunction "2_2") (pintype "passive"))
    )
    (net (code "65") (name "Net-(D13-PadC)") (class "Default")
      (node (ref "D13") (pin "C") (pinfunction "C_C") (pintype "passive"))
      (node (ref "R29") (pin "2") (pinfunction "2_2") (pintype "passive"))
    )
    (net (code "66") (name "Net-(D14-PadC)") (class "Default")
      (node (ref "D14") (pin "C") (pinfunction "C_C") (pintype "passive"))
      (node (ref "R30") (pin "2") (pinfunction "2_2") (pintype "passive"))
    )
    (net (code "67") (name "Net-(D15-PadC)") (class "Default")
      (node (ref "D15") (pin "C") (pinfunction "C_C") (pintype "passive"))
      (node (ref "R31") (pin "2") (pinfunction "2_2") (pintype "passive"))
    )
    (net (code "68") (name "Net-(D16-PadC)") (class "Default")
      (node (ref "D16") (pin "C") (pinfunction "C_C") (pintype "passive"))
      (node (ref "R32") (pin "2") (pinfunction "2_2") (pintype "passive"))
    )
    (net (code "69") (name "Net-(IC2A-B1)") (class "Default")
      (node (ref "D16") (pin "A") (pinfunction "A_A") (pintype "passive"))
      (node (ref "IC2") (pin "18") (pinfunction "B1_18") (pintype "bidirectional"))
      (node (ref "IC4") (pin "18") (pinfunction "B1_18") (pintype "bidirectional"))
      (node (ref "IC8") (pin "3") (pinfunction "Q1_3") (pintype "tri_state"))
      (node (ref "IC9") (pin "18") (pinfunction "B1_18") (pintype "bidirectional"))
    )
    (net (code "70") (name "Net-(IC2A-B2)") (class "Default")
      (node (ref "D15") (pin "A") (pinfunction "A_A") (pintype "passive"))
      (node (ref "IC2") (pin "17") (pinfunction "B2_17") (pintype "bidirectional"))
      (node (ref "IC4") (pin "17") (pinfunction "B2_17") (pintype "bidirectional"))
      (node (ref "IC8") (pin "4") (pinfunction "Q2_4") (pintype "tri_state"))
      (node (ref "IC9") (pin "17") (pinfunction "B2_17") (pintype "bidirectional"))
    )
    (net (code "71") (name "Net-(IC2A-B3)") (class "Default")
      (node (ref "D14") (pin "A") (pinfunction "A_A") (pintype "passive"))
      (node (ref "IC2") (pin "16") (pinfunction "B3_16") (pintype "bidirectional"))
      (node (ref "IC4") (pin "16") (pinfunction "B3_16") (pintype "bidirectional"))
      (node (ref "IC8") (pin "5") (pinfunction "Q3_5") (pintype "tri_state"))
      (node (ref "IC9") (pin "16") (pinfunction "B3_16") (pintype "bidirectional"))
    )
    (net (code "72") (name "Net-(IC2A-B4)") (class "Default")
      (node (ref "D13") (pin "A") (pinfunction "A_A") (pintype "passive"))
      (node (ref "IC2") (pin "15") (pinfunction "B4_15") (pintype "bidirectional"))
      (node (ref "IC4") (pin "15") (pinfunction "B4_15") (pintype "bidirectional"))
      (node (ref "IC8") (pin "6") (pinfunction "Q4_6") (pintype "tri_state"))
      (node (ref "IC9") (pin "15") (pinfunction "B4_15") (pintype "bidirectional"))
    )
    (net (code "73") (name "Net-(IC2A-B5)") (class "Default")
      (node (ref "D12") (pin "A") (pinfunction "A_A") (pintype "passive"))
      (node (ref "IC2") (pin "14") (pinfunction "B5_14") (pintype "bidirectional"))
      (node (ref "IC4") (pin "14") (pinfunction "B5_14") (pintype "bidirectional"))
      (node (ref "IC7") (pin "3") (pinfunction "Q1_3") (pintype "tri_state"))
      (node (ref "IC9") (pin "14") (pinfunction "B5_14") (pintype "bidirectional"))
    )
    (net (code "74") (name "Net-(IC2A-B6)") (class "Default")
      (node (ref "D11") (pin "A") (pinfunction "A_A") (pintype "passive"))
      (node (ref "IC2") (pin "13") (pinfunction "B6_13") (pintype "bidirectional"))
      (node (ref "IC4") (pin "13") (pinfunction "B6_13") (pintype "bidirectional"))
      (node (ref "IC7") (pin "4") (pinfunction "Q2_4") (pintype "tri_state"))
      (node (ref "IC9") (pin "13") (pinfunction "B6_13") (pintype "bidirectional"))
    )
    (net (code "75") (name "Net-(IC2A-B7)") (class "Default")
      (node (ref "D10") (pin "A") (pinfunction "A_A") (pintype "passive"))
      (node (ref "IC2") (pin "12") (pinfunction "B7_12") (pintype "bidirectional"))
      (node (ref "IC4") (pin "12") (pinfunction "B7_12") (pintype "bidirectional"))
      (node (ref "IC7") (pin "5") (pinfunction "Q3_5") (pintype "tri_state"))
      (node (ref "IC9") (pin "12") (pinfunction "B7_12") (pintype "bidirectional"))
    )
    (net (code "76") (name "Net-(IC2A-B8)") (class "Default")
      (node (ref "D9") (pin "A") (pinfunction "A_A") (pintype "passive"))
      (node (ref "IC2") (pin "11") (pinfunction "B8_11") (pintype "bidirectional"))
      (node (ref "IC4") (pin "11") (pinfunction "B8_11") (pintype "bidirectional"))
      (node (ref "IC7") (pin "6") (pinfunction "Q4_6") (pintype "tri_state"))
      (node (ref "IC9") (pin "11") (pinfunction "B8_11") (pintype "bidirectional"))
    )
    (net (code "77") (name "Net-(IC10A-B1)") (class "Default")
      (node (ref "D8") (pin "A") (pinfunction "A_A") (pintype "passive"))
      (node (ref "IC1") (pin "18") (pinfunction "B1_18") (pintype "bidirectional"))
      (node (ref "IC10") (pin "18") (pinfunction "B1_18") (pintype "bidirectional"))
      (node (ref "IC3") (pin "18") (pinfunction "B1_18") (pintype "bidirectional"))
      (node (ref "IC6") (pin "3") (pinfunction "Q1_3") (pintype "tri_state"))
    )
    (net (code "78") (name "Net-(IC10A-B2)") (class "Default")
      (node (ref "D7") (pin "A") (pinfunction "A_A") (pintype "passive"))
      (node (ref "IC1") (pin "17") (pinfunction "B2_17") (pintype "bidirectional"))
      (node (ref "IC10") (pin "17") (pinfunction "B2_17") (pintype "bidirectional"))
      (node (ref "IC3") (pin "17") (pinfunction "B2_17") (pintype "bidirectional"))
      (node (ref "IC6") (pin "4") (pinfunction "Q2_4") (pintype "tri_state"))
    )
    (net (code "79") (name "Net-(IC10A-B3)") (class "Default")
      (node (ref "D6") (pin "A") (pinfunction "A_A") (pintype "passive"))
      (node (ref "IC1") (pin "16") (pinfunction "B3_16") (pintype "bidirectional"))
      (node (ref "IC10") (pin "16") (pinfunction "B3_16") (pintype "bidirectional"))
      (node (ref "IC3") (pin "16") (pinfunction "B3_16") (pintype "bidirectional"))
      (node (ref "IC6") (pin "5") (pinfunction "Q3_5") (pintype "tri_state"))
    )
    (net (code "80") (name "Net-(IC10A-B4)") (class "Default")
      (node (ref "D5") (pin "A") (pinfunction "A_A") (pintype "passive"))
      (node (ref "IC1") (pin "15") (pinfunction "B4_15") (pintype "bidirectional"))
      (node (ref "IC10") (pin "15") (pinfunction "B4_15") (pintype "bidirectional"))
      (node (ref "IC3") (pin "15") (pinfunction "B4_15") (pintype "bidirectional"))
      (node (ref "IC6") (pin "6") (pinfunction "Q4_6") (pintype "tri_state"))
    )
    (net (code "81") (name "Net-(IC10A-B5)") (class "Default")
      (node (ref "D4") (pin "A") (pinfunction "A_A") (pintype "passive"))
      (node (ref "IC1") (pin "14") (pinfunction "B5_14") (pintype "bidirectional"))
      (node (ref "IC10") (pin "14") (pinfunction "B5_14") (pintype "bidirectional"))
      (node (ref "IC3") (pin "14") (pinfunction "B5_14") (pintype "bidirectional"))
      (node (ref "IC5") (pin "3") (pinfunction "Q1_3") (pintype "tri_state"))
    )
    (net (code "82") (name "Net-(IC10A-B6)") (class "Default")
      (node (ref "D3") (pin "A") (pinfunction "A_A") (pintype "passive"))
      (node (ref "IC1") (pin "13") (pinfunction "B6_13") (pintype "bidirectional"))
      (node (ref "IC10") (pin "13") (pinfunction "B6_13") (pintype "bidirectional"))
      (node (ref "IC3") (pin "13") (pinfunction "B6_13") (pintype "bidirectional"))
      (node (ref "IC5") (pin "4") (pinfunction "Q2_4") (pintype "tri_state"))
    )
    (net (code "83") (name "Net-(IC10A-B7)") (class "Default")
      (node (ref "D2") (pin "A") (pinfunction "A_A") (pintype "passive"))
      (node (ref "IC1") (pin "12") (pinfunction "B7_12") (pintype "bidirectional"))
      (node (ref "IC10") (pin "12") (pinfunction "B7_12") (pintype "bidirectional"))
      (node (ref "IC3") (pin "12") (pinfunction "B7_12") (pintype "bidirectional"))
      (node (ref "IC5") (pin "5") (pinfunction "Q3_5") (pintype "tri_state"))
    )
    (net (code "84") (name "Net-(IC10A-B8)") (class "Default")
      (node (ref "D1") (pin "A") (pinfunction "A_A") (pintype "passive"))
      (node (ref "IC1") (pin "11") (pinfunction "B8_11") (pintype "bidirectional"))
      (node (ref "IC10") (pin "11") (pinfunction "B8_11") (pintype "bidirectional"))
      (node (ref "IC3") (pin "11") (pinfunction "B8_11") (pintype "bidirectional"))
      (node (ref "IC5") (pin "6") (pinfunction "Q4_6") (pintype "tri_state"))
    )
    (net (code "85") (name "Net-(IC11A-B1)") (class "Default")
      (node (ref "IC11") (pin "18") (pinfunction "B1_18") (pintype "bidirectional"))
      (node (ref "IC13") (pin "18") (pinfunction "B1_18") (pintype "bidirectional"))
      (node (ref "IC6") (pin "14") (pinfunction "D1_14") (pintype "input"))
      (node (ref "R8") (pin "2") (pinfunction "2_2") (pintype "passive"))
    )
    (net (code "86") (name "Net-(IC11A-B2)") (class "Default")
      (node (ref "IC11") (pin "17") (pinfunction "B2_17") (pintype "bidirectional"))
      (node (ref "IC13") (pin "17") (pinfunction "B2_17") (pintype "bidirectional"))
      (node (ref "IC6") (pin "13") (pinfunction "D2_13") (pintype "input"))
      (node (ref "R7") (pin "2") (pinfunction "2_2") (pintype "passive"))
    )
    (net (code "87") (name "Net-(IC11A-B3)") (class "Default")
      (node (ref "IC11") (pin "16") (pinfunction "B3_16") (pintype "bidirectional"))
      (node (ref "IC13") (pin "16") (pinfunction "B3_16") (pintype "bidirectional"))
      (node (ref "IC6") (pin "12") (pinfunction "D3_12") (pintype "input"))
      (node (ref "R6") (pin "2") (pinfunction "2_2") (pintype "passive"))
    )
    (net (code "88") (name "Net-(IC11A-B4)") (class "Default")
      (node (ref "IC11") (pin "15") (pinfunction "B4_15") (pintype "bidirectional"))
      (node (ref "IC13") (pin "15") (pinfunction "B4_15") (pintype "bidirectional"))
      (node (ref "IC6") (pin "11") (pinfunction "D4_11") (pintype "input"))
      (node (ref "R5") (pin "2") (pinfunction "2_2") (pintype "passive"))
    )
    (net (code "89") (name "Net-(IC11A-B5)") (class "Default")
      (node (ref "IC11") (pin "14") (pinfunction "B5_14") (pintype "bidirectional"))
      (node (ref "IC13") (pin "14") (pinfunction "B5_14") (pintype "bidirectional"))
      (node (ref "IC5") (pin "14") (pinfunction "D1_14") (pintype "input"))
      (node (ref "R4") (pin "2") (pinfunction "2_2") (pintype "passive"))
    )
    (net (code "90") (name "Net-(IC11A-B6)") (class "Default")
      (node (ref "IC11") (pin "13") (pinfunction "B6_13") (pintype "bidirectional"))
      (node (ref "IC13") (pin "13") (pinfunction "B6_13") (pintype "bidirectional"))
      (node (ref "IC5") (pin "13") (pinfunction "D2_13") (pintype "input"))
      (node (ref "R3") (pin "2") (pinfunction "2_2") (pintype "passive"))
    )
    (net (code "91") (name "Net-(IC11A-B7)") (class "Default")
      (node (ref "IC11") (pin "12") (pinfunction "B7_12") (pintype "bidirectional"))
      (node (ref "IC13") (pin "12") (pinfunction "B7_12") (pintype "bidirectional"))
      (node (ref "IC5") (pin "12") (pinfunction "D3_12") (pintype "input"))
      (node (ref "R2") (pin "2") (pinfunction "2_2") (pintype "passive"))
    )
    (net (code "92") (name "Net-(IC11A-B8)") (class "Default")
      (node (ref "IC11") (pin "11") (pinfunction "B8_11") (pintype "bidirectional"))
      (node (ref "IC13") (pin "11") (pinfunction "B8_11") (pintype "bidirectional"))
      (node (ref "IC5") (pin "11") (pinfunction "D4_11") (pintype "input"))
      (node (ref "R1") (pin "2") (pinfunction "2_2") (pintype "passive"))
    )
    (net (code "93") (name "Net-(IC12A-B1)") (class "Default")
      (node (ref "IC12") (pin "18") (pinfunction "B1_18") (pintype "bidirectional"))
      (node (ref "IC14") (pin "18") (pinfunction "B1_18") (pintype "bidirectional"))
      (node (ref "IC8") (pin "14") (pinfunction "D1_14") (pintype "input"))
      (node (ref "R16") (pin "2") (pinfunction "2_2") (pintype "passive"))
    )
    (net (code "94") (name "Net-(IC12A-B2)") (class "Default")
      (node (ref "IC12") (pin "17") (pinfunction "B2_17") (pintype "bidirectional"))
      (node (ref "IC14") (pin "17") (pinfunction "B2_17") (pintype "bidirectional"))
      (node (ref "IC8") (pin "13") (pinfunction "D2_13") (pintype "input"))
      (node (ref "R15") (pin "2") (pinfunction "2_2") (pintype "passive"))
    )
    (net (code "95") (name "Net-(IC12A-B3)") (class "Default")
      (node (ref "IC12") (pin "16") (pinfunction "B3_16") (pintype "bidirectional"))
      (node (ref "IC14") (pin "16") (pinfunction "B3_16") (pintype "bidirectional"))
      (node (ref "IC8") (pin "12") (pinfunction "D3_12") (pintype "input"))
      (node (ref "R14") (pin "2") (pinfunction "2_2") (pintype "passive"))
    )
    (net (code "96") (name "Net-(IC12A-B4)") (class "Default")
      (node (ref "IC12") (pin "15") (pinfunction "B4_15") (pintype "bidirectional"))
      (node (ref "IC14") (pin "15") (pinfunction "B4_15") (pintype "bidirectional"))
      (node (ref "IC8") (pin "11") (pinfunction "D4_11") (pintype "input"))
      (node (ref "R13") (pin "2") (pinfunction "2_2") (pintype "passive"))
    )
    (net (code "97") (name "Net-(IC12A-B5)") (class "Default")
      (node (ref "IC12") (pin "14") (pinfunction "B5_14") (pintype "bidirectional"))
      (node (ref "IC14") (pin "14") (pinfunction "B5_14") (pintype "bidirectional"))
      (node (ref "IC7") (pin "14") (pinfunction "D1_14") (pintype "input"))
      (node (ref "R12") (pin "2") (pinfunction "2_2") (pintype "passive"))
    )
    (net (code "98") (name "Net-(IC12A-B6)") (class "Default")
      (node (ref "IC12") (pin "13") (pinfunction "B6_13") (pintype "bidirectional"))
      (node (ref "IC14") (pin "13") (pinfunction "B6_13") (pintype "bidirectional"))
      (node (ref "IC7") (pin "13") (pinfunction "D2_13") (pintype "input"))
      (node (ref "R11") (pin "2") (pinfunction "2_2") (pintype "passive"))
    )
    (net (code "99") (name "Net-(IC12A-B7)") (class "Default")
      (node (ref "IC12") (pin "12") (pinfunction "B7_12") (pintype "bidirectional"))
      (node (ref "IC14") (pin "12") (pinfunction "B7_12") (pintype "bidirectional"))
      (node (ref "IC7") (pin "12") (pinfunction "D3_12") (pintype "input"))
      (node (ref "R10") (pin "2") (pinfunction "2_2") (pintype "passive"))
    )
    (net (code "100") (name "Net-(IC12A-B8)") (class "Default")
      (node (ref "IC12") (pin "11") (pinfunction "B8_11") (pintype "bidirectional"))
      (node (ref "IC14") (pin "11") (pinfunction "B8_11") (pintype "bidirectional"))
      (node (ref "IC7") (pin "11") (pinfunction "D4_11") (pintype "input"))
      (node (ref "R9") (pin "2") (pinfunction "2_2") (pintype "passive"))
    )
    (net (code "101") (name "Net-(IC16A-O)") (class "Default")
      (node (ref "IC16") (pin "3") (pinfunction "O_3") (pintype "open_collector"))
      (node (ref "IC7") (pin "10") (pinfunction "G2_10") (pintype "input"))
      (node (ref "IC7") (pin "9") (pinfunction "G1_9") (pintype "input"))
      (node (ref "IC8") (pin "10") (pinfunction "G2_10") (pintype "input"))
      (node (ref "IC8") (pin "9") (pinfunction "G1_9") (pintype "input"))
    )
    (net (code "102") (name "Net-(IC16B-O)") (class "Default")
      (node (ref "IC16") (pin "4") (pinfunction "O_4") (pintype "open_collector"))
      (node (ref "IC5") (pin "10") (pinfunction "G2_10") (pintype "input"))
      (node (ref "IC5") (pin "9") (pinfunction "G1_9") (pintype "input"))
      (node (ref "IC6") (pin "10") (pinfunction "G2_10") (pintype "input"))
      (node (ref "IC6") (pin "9") (pinfunction "G1_9") (pintype "input"))
    )
    (net (code "103") (name "Net-(LED_CLK-K2)") (class "Default")
      (node (ref "LED_CLK") (pin "1") (pinfunction "K2_1") (pintype "passive"))
      (node (ref "R33") (pin "2") (pinfunction "2_2") (pintype "passive"))
    )
    (net (code "104") (name "Net-(LED_RESET-K2)") (class "Default")
      (node (ref "LED_RESET") (pin "1") (pinfunction "K2_1") (pintype "passive"))
      (node (ref "R34") (pin "2") (pinfunction "2_2") (pintype "passive"))
    )
    (net (code "105") (name "Net-(LED_XFER_ASSERT_ADDR-K2)") (class "Default")
      (node (ref "LED_XFER_ASSERT_ADDR") (pin "1") (pinfunction "K2_1") (pintype "passive"))
      (node (ref "R39") (pin "1") (pinfunction "1_1") (pintype "passive"))
    )
    (net (code "106") (name "Net-(LED_XFER_ASSERT_XFER-K2)") (class "Default")
      (node (ref "LED_XFER_ASSERT_XFER") (pin "1") (pinfunction "K2_1") (pintype "passive"))
      (node (ref "R38") (pin "1") (pinfunction "1_1") (pintype "passive"))
    )
    (net (code "107") (name "Net-(LED_XFER_LOAD_XFER-K2)") (class "Default")
      (node (ref "LED_XFER_LOAD_XFER") (pin "1") (pinfunction "K2_1") (pintype "passive"))
      (node (ref "R35") (pin "1") (pinfunction "1_1") (pintype "passive"))
    )
    (net (code "108") (name "Net-(LED_XFER_L_ASSERT-K2)") (class "Default")
      (node (ref "LED_XFER_L_ASSERT") (pin "1") (pinfunction "K2_1") (pintype "passive"))
      (node (ref "R41") (pin "1") (pinfunction "1_1") (pintype "passive"))
    )
    (net (code "109") (name "Net-(LED_XFER_L_LOAD-K2)") (class "Default")
      (node (ref "LED_XFER_L_LOAD") (pin "1") (pinfunction "K2_1") (pintype "passive"))
      (node (ref "R37") (pin "1") (pinfunction "1_1") (pintype "passive"))
    )
    (net (code "110") (name "Net-(LED_XFER_R_ASSERT-K2)") (class "Default")
      (node (ref "LED_XFER_R_ASSERT") (pin "1") (pinfunction "K2_1") (pintype "passive"))
      (node (ref "R40") (pin "1") (pinfunction "1_1") (pintype "passive"))
    )
    (net (code "111") (name "Net-(LED_XFER_R_LOAD-K2)") (class "Default")
      (node (ref "LED_XFER_R_LOAD") (pin "1") (pinfunction "K2_1") (pintype "passive"))
      (node (ref "R36") (pin "1") (pinfunction "1_1") (pintype "passive"))
    )
    (net (code "112") (name "VCC") (class "Default")
      (node (ref "C1") (pin "2") (pinfunction "2_2") (pintype "passive"))
      (node (ref "C10") (pin "2") (pinfunction "2_2") (pintype "passive"))
      (node (ref "C11") (pin "2") (pinfunction "2_2") (pintype "passive"))
      (node (ref "C12") (pin "2") (pinfunction "2_2") (pintype "passive"))
      (node (ref "C13") (pin "2") (pinfunction "2_2") (pintype "passive"))
      (node (ref "C14") (pin "2") (pinfunction "2_2") (pintype "passive"))
      (node (ref "C15") (pin "2") (pinfunction "2_2") (pintype "passive"))
      (node (ref "C16") (pin "2") (pinfunction "2_2") (pintype "passive"))
      (node (ref "C17") (pin "2") (pinfunction "2_2") (pintype "passive"))
      (node (ref "C18") (pin "2") (pinfunction "2_2") (pintype "passive"))
      (node (ref "C19") (pin "2") (pinfunction "2_2") (pintype "passive"))
      (node (ref "C2") (pin "2") (pinfunction "2_2") (pintype "passive"))
      (node (ref "C3") (pin "2") (pinfunction "2_2") (pintype "passive"))
      (node (ref "C4") (pin "2") (pinfunction "2_2") (pintype "passive"))
      (node (ref "C5") (pin "2") (pinfunction "2_2") (pintype "passive"))
      (node (ref "C6") (pin "2") (pinfunction "2_2") (pintype "passive"))
      (node (ref "C7") (pin "2") (pinfunction "2_2") (pintype "passive"))
      (node (ref "C8") (pin "2") (pinfunction "2_2") (pintype "passive"))
      (node (ref "C9") (pin "2") (pinfunction "2_2") (pintype "passive"))
      (node (ref "IC1") (pin "20") (pinfunction "VCC_20") (pintype "power_in"))
      (node (ref "IC10") (pin "20") (pinfunction "VCC_20") (pintype "power_in"))
      (node (ref "IC11") (pin "1") (pinfunction "DIR_1") (pintype "input"))
      (node (ref "IC11") (pin "20") (pinfunction "VCC_20") (pintype "power_in"))
      (node (ref "IC12") (pin "1") (pinfunction "DIR_1") (pintype "input"))
      (node (ref "IC12") (pin "20") (pinfunction "VCC_20") (pintype "power_in"))
      (node (ref "IC13") (pin "1") (pinfunction "DIR_1") (pintype "input"))
      (node (ref "IC13") (pin "20") (pinfunction "VCC_20") (pintype "power_in"))
      (node (ref "IC14") (pin "1") (pinfunction "DIR_1") (pintype "input"))
      (node (ref "IC14") (pin "20") (pinfunction "VCC_20") (pintype "power_in"))
      (node (ref "IC16") (pin "12") (pinfunction "I0_12") (pintype "input"))
      (node (ref "IC16") (pin "13") (pinfunction "I1_13") (pintype "input"))
      (node (ref "IC16") (pin "14") (pinfunction "VCC_14") (pintype "power_in"))
      (node (ref "IC16") (pin "8") (pinfunction "I0_8") (pintype "input"))
      (node (ref "IC16") (pin "9") (pinfunction "I1_9") (pintype "input"))
      (node (ref "IC2") (pin "20") (pinfunction "VCC_20") (pintype "power_in"))
      (node (ref "IC3") (pin "20") (pinfunction "VCC_20") (pintype "power_in"))
      (node (ref "IC4") (pin "20") (pinfunction "VCC_20") (pintype "power_in"))
      (node (ref "IC5") (pin "16") (pinfunction "VCC_16") (pintype "power_in"))
      (node (ref "IC6") (pin "16") (pinfunction "VCC_16") (pintype "power_in"))
      (node (ref "IC7") (pin "16") (pinfunction "VCC_16") (pintype "power_in"))
      (node (ref "IC8") (pin "16") (pinfunction "VCC_16") (pintype "power_in"))
      (node (ref "IC9") (pin "20") (pinfunction "VCC_20") (pintype "power_in"))
      (node (ref "LED_XFER_ASSERT_ADDR") (pin "2") (pinfunction "A2_2") (pintype "passive"))
      (node (ref "LED_XFER_ASSERT_XFER") (pin "2") (pinfunction "A2_2") (pintype "passive"))
      (node (ref "LED_XFER_LOAD_XFER") (pin "2") (pinfunction "A2_2") (pintype "passive"))
      (node (ref "LED_XFER_L_ASSERT") (pin "2") (pinfunction "A2_2") (pintype "passive"))
      (node (ref "LED_XFER_L_LOAD") (pin "2") (pinfunction "A2_2") (pintype "passive"))
      (node (ref "LED_XFER_R_ASSERT") (pin "2") (pinfunction "A2_2") (pintype "passive"))
      (node (ref "LED_XFER_R_LOAD") (pin "2") (pinfunction "A2_2") (pintype "passive"))
      (node (ref "SV_XFER_1") (pin "1") (pinfunction "1_1") (pintype "passive"))
      (node (ref "SV_XFER_1") (pin "36") (pinfunction "36_36") (pintype "passive"))
      (node (ref "SV_XFER_2") (pin "1") (pinfunction "1_1") (pintype "passive"))
      (node (ref "SV_XFER_2") (pin "36") (pinfunction "36_36") (pintype "passive"))
      (node (ref "SV_XFER_3") (pin "1") (pinfunction "1_1") (pintype "passive"))
      (node (ref "SV_XFER_3") (pin "36") (pinfunction "36_36") (pintype "passive"))
      (node (ref "SV_XFER_4") (pin "1") (pinfunction "1_1") (pintype "passive"))
      (node (ref "SV_XFER_4") (pin "36") (pinfunction "36_36") (pintype "passive"))
    )
    (net (code "113") (name "unconnected-(IC16C-O-Pad10)") (class "Default")
      (node (ref "IC16") (pin "10") (pinfunction "O_10") (pintype "open_collector"))
    )
    (net (code "114") (name "unconnected-(IC16D-O-Pad11)") (class "Default")
      (node (ref "IC16") (pin "11") (pinfunction "O_11") (pintype "open_collector"))
    )
    (net (code "115") (name "unconnected-(SV_XFER_2-Pad3)") (class "Default")
      (node (ref "SV_XFER_2") (pin "3") (pinfunction "3_3") (pintype "passive"))
    )
    (net (code "116") (name "unconnected-(SV_XFER_2-Pad5)") (class "Default")
      (node (ref "SV_XFER_2") (pin "5") (pinfunction "5_5") (pintype "passive"))
    )
    (net (code "117") (name "unconnected-(SV_XFER_2-Pad7)") (class "Default")
      (node (ref "SV_XFER_2") (pin "7") (pinfunction "7_7") (pintype "passive"))
    )
    (net (code "118") (name "unconnected-(SV_XFER_2-Pad9)") (class "Default")
      (node (ref "SV_XFER_2") (pin "9") (pinfunction "9_9") (pintype "passive"))
    )
    (net (code "119") (name "unconnected-(SV_XFER_2-Pad11)") (class "Default")
      (node (ref "SV_XFER_2") (pin "11") (pinfunction "11_11") (pintype "passive"))
    )
    (net (code "120") (name "unconnected-(SV_XFER_2-Pad12)") (class "Default")
      (node (ref "SV_XFER_2") (pin "12") (pinfunction "12_12") (pintype "passive"))
    )
    (net (code "121") (name "unconnected-(SV_XFER_2-Pad13)") (class "Default")
      (node (ref "SV_XFER_2") (pin "13") (pinfunction "13_13") (pintype "passive"))
    )
    (net (code "122") (name "unconnected-(SV_XFER_2-Pad14)") (class "Default")
      (node (ref "SV_XFER_2") (pin "14") (pinfunction "14_14") (pintype "passive"))
    )
    (net (code "123") (name "unconnected-(SV_XFER_2-Pad15)") (class "Default")
      (node (ref "SV_XFER_2") (pin "15") (pinfunction "15_15") (pintype "passive"))
    )
    (net (code "124") (name "unconnected-(SV_XFER_2-Pad16)") (class "Default")
      (node (ref "SV_XFER_2") (pin "16") (pinfunction "16_16") (pintype "passive"))
    )
    (net (code "125") (name "unconnected-(SV_XFER_2-Pad17)") (class "Default")
      (node (ref "SV_XFER_2") (pin "17") (pinfunction "17_17") (pintype "passive"))
    )
    (net (code "126") (name "unconnected-(SV_XFER_2-Pad18)") (class "Default")
      (node (ref "SV_XFER_2") (pin "18") (pinfunction "18_18") (pintype "passive"))
    )
    (net (code "127") (name "unconnected-(SV_XFER_2-Pad27)") (class "Default")
      (node (ref "SV_XFER_2") (pin "27") (pinfunction "27_27") (pintype "passive"))
    )
    (net (code "128") (name "unconnected-(SV_XFER_3-Pad3)") (class "Default")
      (node (ref "SV_XFER_3") (pin "3") (pinfunction "3_3") (pintype "passive"))
    )
    (net (code "129") (name "unconnected-(SV_XFER_3-Pad4)") (class "Default")
      (node (ref "SV_XFER_3") (pin "4") (pinfunction "4_4") (pintype "passive"))
    )
    (net (code "130") (name "unconnected-(SV_XFER_3-Pad5)") (class "Default")
      (node (ref "SV_XFER_3") (pin "5") (pinfunction "5_5") (pintype "passive"))
    )
    (net (code "131") (name "unconnected-(SV_XFER_3-Pad6)") (class "Default")
      (node (ref "SV_XFER_3") (pin "6") (pinfunction "6_6") (pintype "passive"))
    )
    (net (code "132") (name "unconnected-(SV_XFER_3-Pad7)") (class "Default")
      (node (ref "SV_XFER_3") (pin "7") (pinfunction "7_7") (pintype "passive"))
    )
    (net (code "133") (name "unconnected-(SV_XFER_3-Pad8)") (class "Default")
      (node (ref "SV_XFER_3") (pin "8") (pinfunction "8_8") (pintype "passive"))
    )
    (net (code "134") (name "unconnected-(SV_XFER_3-Pad9)") (class "Default")
      (node (ref "SV_XFER_3") (pin "9") (pinfunction "9_9") (pintype "passive"))
    )
    (net (code "135") (name "unconnected-(SV_XFER_3-Pad10)") (class "Default")
      (node (ref "SV_XFER_3") (pin "10") (pinfunction "10_10") (pintype "passive"))
    )
    (net (code "136") (name "unconnected-(SV_XFER_3-Pad11)") (class "Default")
      (node (ref "SV_XFER_3") (pin "11") (pinfunction "11_11") (pintype "passive"))
    )
    (net (code "137") (name "unconnected-(SV_XFER_3-Pad12)") (class "Default")
      (node (ref "SV_XFER_3") (pin "12") (pinfunction "12_12") (pintype "passive"))
    )
    (net (code "138") (name "unconnected-(SV_XFER_3-Pad13)") (class "Default")
      (node (ref "SV_XFER_3") (pin "13") (pinfunction "13_13") (pintype "passive"))
    )
    (net (code "139") (name "unconnected-(SV_XFER_3-Pad14)") (class "Default")
      (node (ref "SV_XFER_3") (pin "14") (pinfunction "14_14") (pintype "passive"))
    )
    (net (code "140") (name "unconnected-(SV_XFER_3-Pad15)") (class "Default")
      (node (ref "SV_XFER_3") (pin "15") (pinfunction "15_15") (pintype "passive"))
    )
    (net (code "141") (name "unconnected-(SV_XFER_3-Pad16)") (class "Default")
      (node (ref "SV_XFER_3") (pin "16") (pinfunction "16_16") (pintype "passive"))
    )
    (net (code "142") (name "unconnected-(SV_XFER_3-Pad17)") (class "Default")
      (node (ref "SV_XFER_3") (pin "17") (pinfunction "17_17") (pintype "passive"))
    )
    (net (code "143") (name "unconnected-(SV_XFER_3-Pad18)") (class "Default")
      (node (ref "SV_XFER_3") (pin "18") (pinfunction "18_18") (pintype "passive"))
    )
    (net (code "144") (name "unconnected-(SV_XFER_3-Pad19)") (class "Default")
      (node (ref "SV_XFER_3") (pin "19") (pinfunction "19_19") (pintype "passive"))
    )
    (net (code "145") (name "unconnected-(SV_XFER_3-Pad20)") (class "Default")
      (node (ref "SV_XFER_3") (pin "20") (pinfunction "20_20") (pintype "passive"))
    )
    (net (code "146") (name "unconnected-(SV_XFER_3-Pad21)") (class "Default")
      (node (ref "SV_XFER_3") (pin "21") (pinfunction "21_21") (pintype "passive"))
    )
    (net (code "147") (name "unconnected-(SV_XFER_3-Pad22)") (class "Default")
      (node (ref "SV_XFER_3") (pin "22") (pinfunction "22_22") (pintype "passive"))
    )
    (net (code "148") (name "unconnected-(SV_XFER_3-Pad23)") (class "Default")
      (node (ref "SV_XFER_3") (pin "23") (pinfunction "23_23") (pintype "passive"))
    )
    (net (code "149") (name "unconnected-(SV_XFER_3-Pad24)") (class "Default")
      (node (ref "SV_XFER_3") (pin "24") (pinfunction "24_24") (pintype "passive"))
    )
    (net (code "150") (name "unconnected-(SV_XFER_3-Pad25)") (class "Default")
      (node (ref "SV_XFER_3") (pin "25") (pinfunction "25_25") (pintype "passive"))
    )
    (net (code "151") (name "unconnected-(SV_XFER_3-Pad26)") (class "Default")
      (node (ref "SV_XFER_3") (pin "26") (pinfunction "26_26") (pintype "passive"))
    )
    (net (code "152") (name "unconnected-(SV_XFER_3-Pad27)") (class "Default")
      (node (ref "SV_XFER_3") (pin "27") (pinfunction "27_27") (pintype "passive"))
    )
    (net (code "153") (name "unconnected-(SV_XFER_3-Pad28)") (class "Default")
      (node (ref "SV_XFER_3") (pin "28") (pinfunction "28_28") (pintype "passive"))
    )
    (net (code "154") (name "unconnected-(SV_XFER_3-Pad29)") (class "Default")
      (node (ref "SV_XFER_3") (pin "29") (pinfunction "29_29") (pintype "passive"))
    )
    (net (code "155") (name "unconnected-(SV_XFER_3-Pad30)") (class "Default")
      (node (ref "SV_XFER_3") (pin "30") (pinfunction "30_30") (pintype "passive"))
    )
    (net (code "156") (name "unconnected-(SV_XFER_3-Pad31)") (class "Default")
      (node (ref "SV_XFER_3") (pin "31") (pinfunction "31_31") (pintype "passive"))
    )
    (net (code "157") (name "unconnected-(SV_XFER_3-Pad32)") (class "Default")
      (node (ref "SV_XFER_3") (pin "32") (pinfunction "32_32") (pintype "passive"))
    )
    (net (code "158") (name "unconnected-(SV_XFER_3-Pad33)") (class "Default")
      (node (ref "SV_XFER_3") (pin "33") (pinfunction "33_33") (pintype "passive"))
    )
    (net (code "159") (name "unconnected-(SV_XFER_3-Pad34)") (class "Default")
      (node (ref "SV_XFER_3") (pin "34") (pinfunction "34_34") (pintype "passive"))
    )
    (net (code "160") (name "unconnected-(SV_XFER_4-Pad3)") (class "Default")
      (node (ref "SV_XFER_4") (pin "3") (pinfunction "3_3") (pintype "passive"))
    )
    (net (code "161") (name "unconnected-(SV_XFER_4-Pad4)") (class "Default")
      (node (ref "SV_XFER_4") (pin "4") (pinfunction "4_4") (pintype "passive"))
    )
    (net (code "162") (name "unconnected-(SV_XFER_4-Pad5)") (class "Default")
      (node (ref "SV_XFER_4") (pin "5") (pinfunction "5_5") (pintype "passive"))
    )
    (net (code "163") (name "unconnected-(SV_XFER_4-Pad6)") (class "Default")
      (node (ref "SV_XFER_4") (pin "6") (pinfunction "6_6") (pintype "passive"))
    )
    (net (code "164") (name "unconnected-(SV_XFER_4-Pad7)") (class "Default")
      (node (ref "SV_XFER_4") (pin "7") (pinfunction "7_7") (pintype "passive"))
    )
    (net (code "165") (name "unconnected-(SV_XFER_4-Pad8)") (class "Default")
      (node (ref "SV_XFER_4") (pin "8") (pinfunction "8_8") (pintype "passive"))
    )
    (net (code "166") (name "unconnected-(SV_XFER_4-Pad9)") (class "Default")
      (node (ref "SV_XFER_4") (pin "9") (pinfunction "9_9") (pintype "passive"))
    )
    (net (code "167") (name "unconnected-(SV_XFER_4-Pad10)") (class "Default")
      (node (ref "SV_XFER_4") (pin "10") (pinfunction "10_10") (pintype "passive"))
    )
    (net (code "168") (name "unconnected-(SV_XFER_4-Pad11)") (class "Default")
      (node (ref "SV_XFER_4") (pin "11") (pinfunction "11_11") (pintype "passive"))
    )
    (net (code "169") (name "unconnected-(SV_XFER_4-Pad12)") (class "Default")
      (node (ref "SV_XFER_4") (pin "12") (pinfunction "12_12") (pintype "passive"))
    )
    (net (code "170") (name "unconnected-(SV_XFER_4-Pad13)") (class "Default")
      (node (ref "SV_XFER_4") (pin "13") (pinfunction "13_13") (pintype "passive"))
    )
    (net (code "171") (name "unconnected-(SV_XFER_4-Pad14)") (class "Default")
      (node (ref "SV_XFER_4") (pin "14") (pinfunction "14_14") (pintype "passive"))
    )
    (net (code "172") (name "unconnected-(SV_XFER_4-Pad15)") (class "Default")
      (node (ref "SV_XFER_4") (pin "15") (pinfunction "15_15") (pintype "passive"))
    )
    (net (code "173") (name "unconnected-(SV_XFER_4-Pad16)") (class "Default")
      (node (ref "SV_XFER_4") (pin "16") (pinfunction "16_16") (pintype "passive"))
    )
    (net (code "174") (name "unconnected-(SV_XFER_4-Pad17)") (class "Default")
      (node (ref "SV_XFER_4") (pin "17") (pinfunction "17_17") (pintype "passive"))
    )
    (net (code "175") (name "unconnected-(SV_XFER_4-Pad18)") (class "Default")
      (node (ref "SV_XFER_4") (pin "18") (pinfunction "18_18") (pintype "passive"))
    )
    (net (code "176") (name "unconnected-(SV_XFER_4-Pad19)") (class "Default")
      (node (ref "SV_XFER_4") (pin "19") (pinfunction "19_19") (pintype "passive"))
    )
    (net (code "177") (name "unconnected-(SV_XFER_4-Pad20)") (class "Default")
      (node (ref "SV_XFER_4") (pin "20") (pinfunction "20_20") (pintype "passive"))
    )
    (net (code "178") (name "unconnected-(SV_XFER_4-Pad21)") (class "Default")
      (node (ref "SV_XFER_4") (pin "21") (pinfunction "21_21") (pintype "passive"))
    )
    (net (code "179") (name "unconnected-(SV_XFER_4-Pad22)") (class "Default")
      (node (ref "SV_XFER_4") (pin "22") (pinfunction "22_22") (pintype "passive"))
    )
    (net (code "180") (name "unconnected-(SV_XFER_4-Pad23)") (class "Default")
      (node (ref "SV_XFER_4") (pin "23") (pinfunction "23_23") (pintype "passive"))
    )
    (net (code "181") (name "unconnected-(SV_XFER_4-Pad24)") (class "Default")
      (node (ref "SV_XFER_4") (pin "24") (pinfunction "24_24") (pintype "passive"))
    )
    (net (code "182") (name "unconnected-(SV_XFER_4-Pad25)") (class "Default")
      (node (ref "SV_XFER_4") (pin "25") (pinfunction "25_25") (pintype "passive"))
    )
    (net (code "183") (name "unconnected-(SV_XFER_4-Pad26)") (class "Default")
      (node (ref "SV_XFER_4") (pin "26") (pinfunction "26_26") (pintype "passive"))
    )
    (net (code "184") (name "unconnected-(SV_XFER_4-Pad27)") (class "Default")
      (node (ref "SV_XFER_4") (pin "27") (pinfunction "27_27") (pintype "passive"))
    )
    (net (code "185") (name "unconnected-(SV_XFER_4-Pad28)") (class "Default")
      (node (ref "SV_XFER_4") (pin "28") (pinfunction "28_28") (pintype "passive"))
    )
    (net (code "186") (name "unconnected-(SV_XFER_4-Pad29)") (class "Default")
      (node (ref "SV_XFER_4") (pin "29") (pinfunction "29_29") (pintype "passive"))
    )
    (net (code "187") (name "unconnected-(SV_XFER_4-Pad30)") (class "Default")
      (node (ref "SV_XFER_4") (pin "30") (pinfunction "30_30") (pintype "passive"))
    )
    (net (code "188") (name "unconnected-(SV_XFER_4-Pad31)") (class "Default")
      (node (ref "SV_XFER_4") (pin "31") (pinfunction "31_31") (pintype "passive"))
    )
    (net (code "189") (name "unconnected-(SV_XFER_4-Pad32)") (class "Default")
      (node (ref "SV_XFER_4") (pin "32") (pinfunction "32_32") (pintype "passive"))
    )
    (net (code "190") (name "unconnected-(SV_XFER_4-Pad33)") (class "Default")
      (node (ref "SV_XFER_4") (pin "33") (pinfunction "33_33") (pintype "passive"))
    )
    (net (code "191") (name "unconnected-(SV_XFER_4-Pad34)") (class "Default")
      (node (ref "SV_XFER_4") (pin "34") (pinfunction "34_34") (pintype "passive"))
    )
  )
)
